# controller_tcan334gdcnt.net
KiCad netlist of a schematic drawn in EAGLE
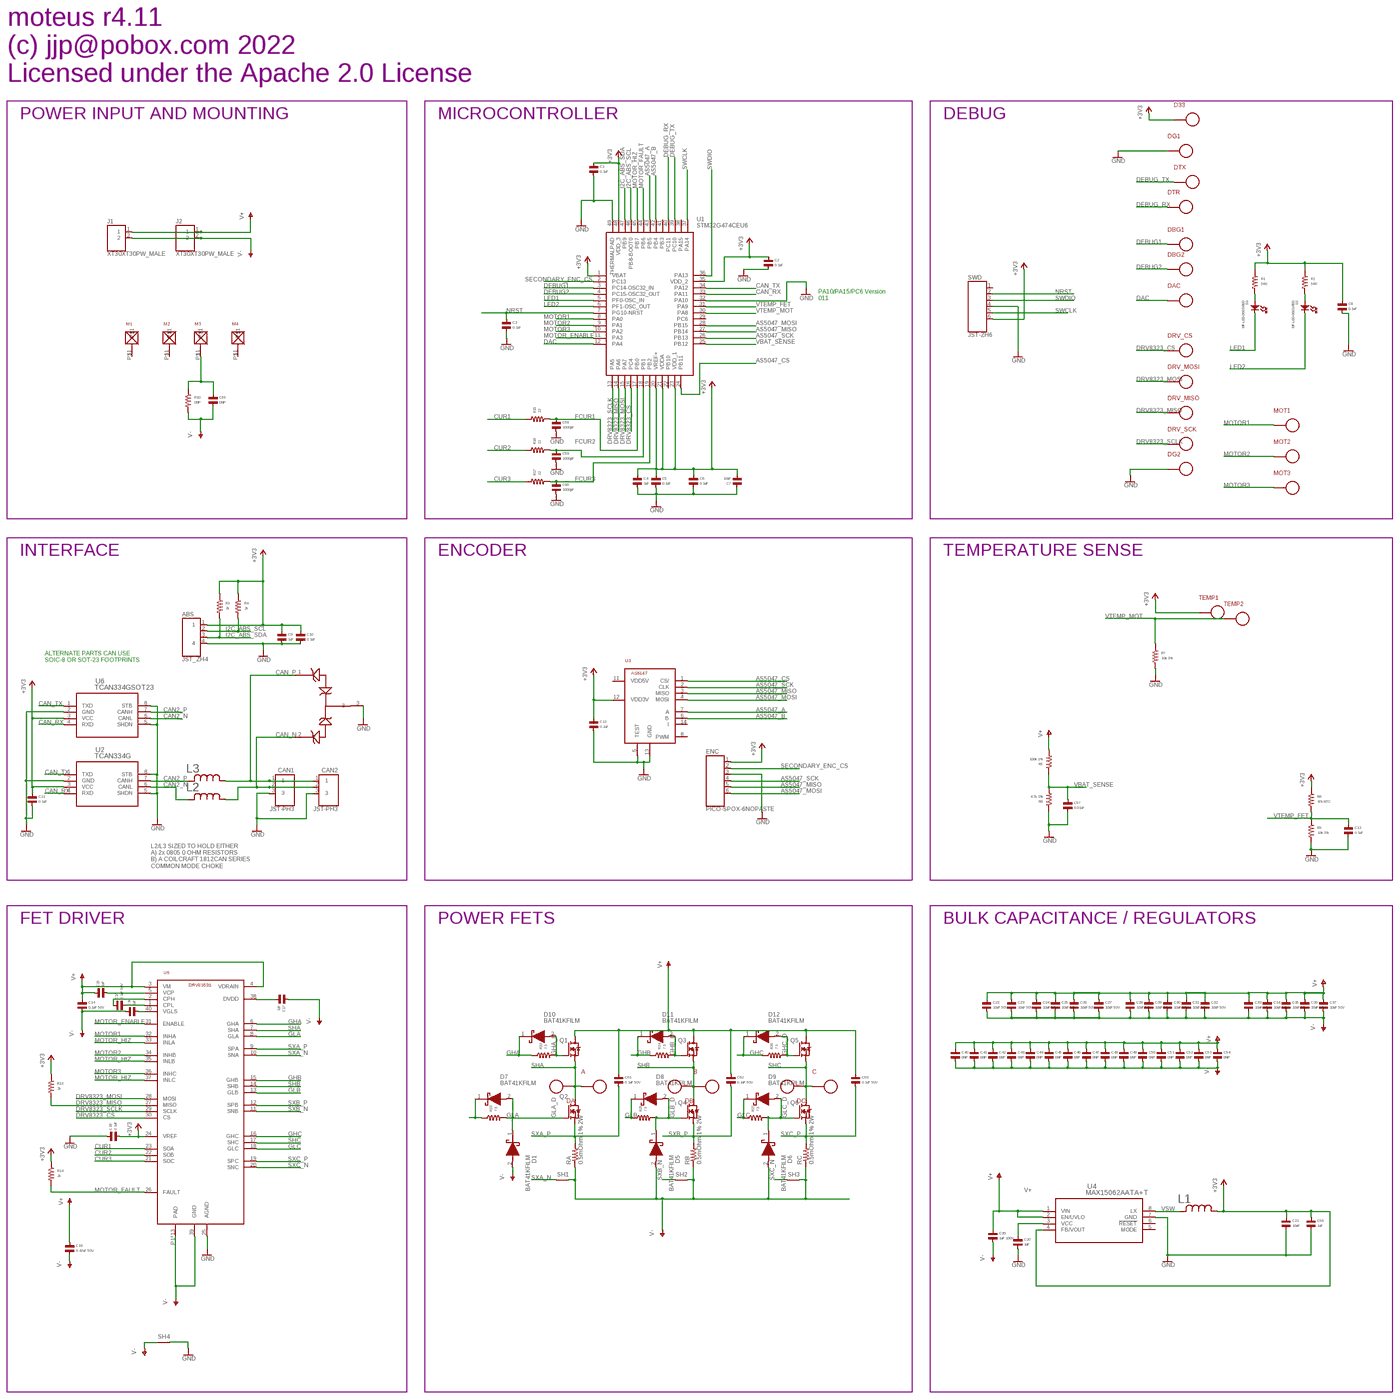
[diagram p0: schematic, sheet 1, overview]
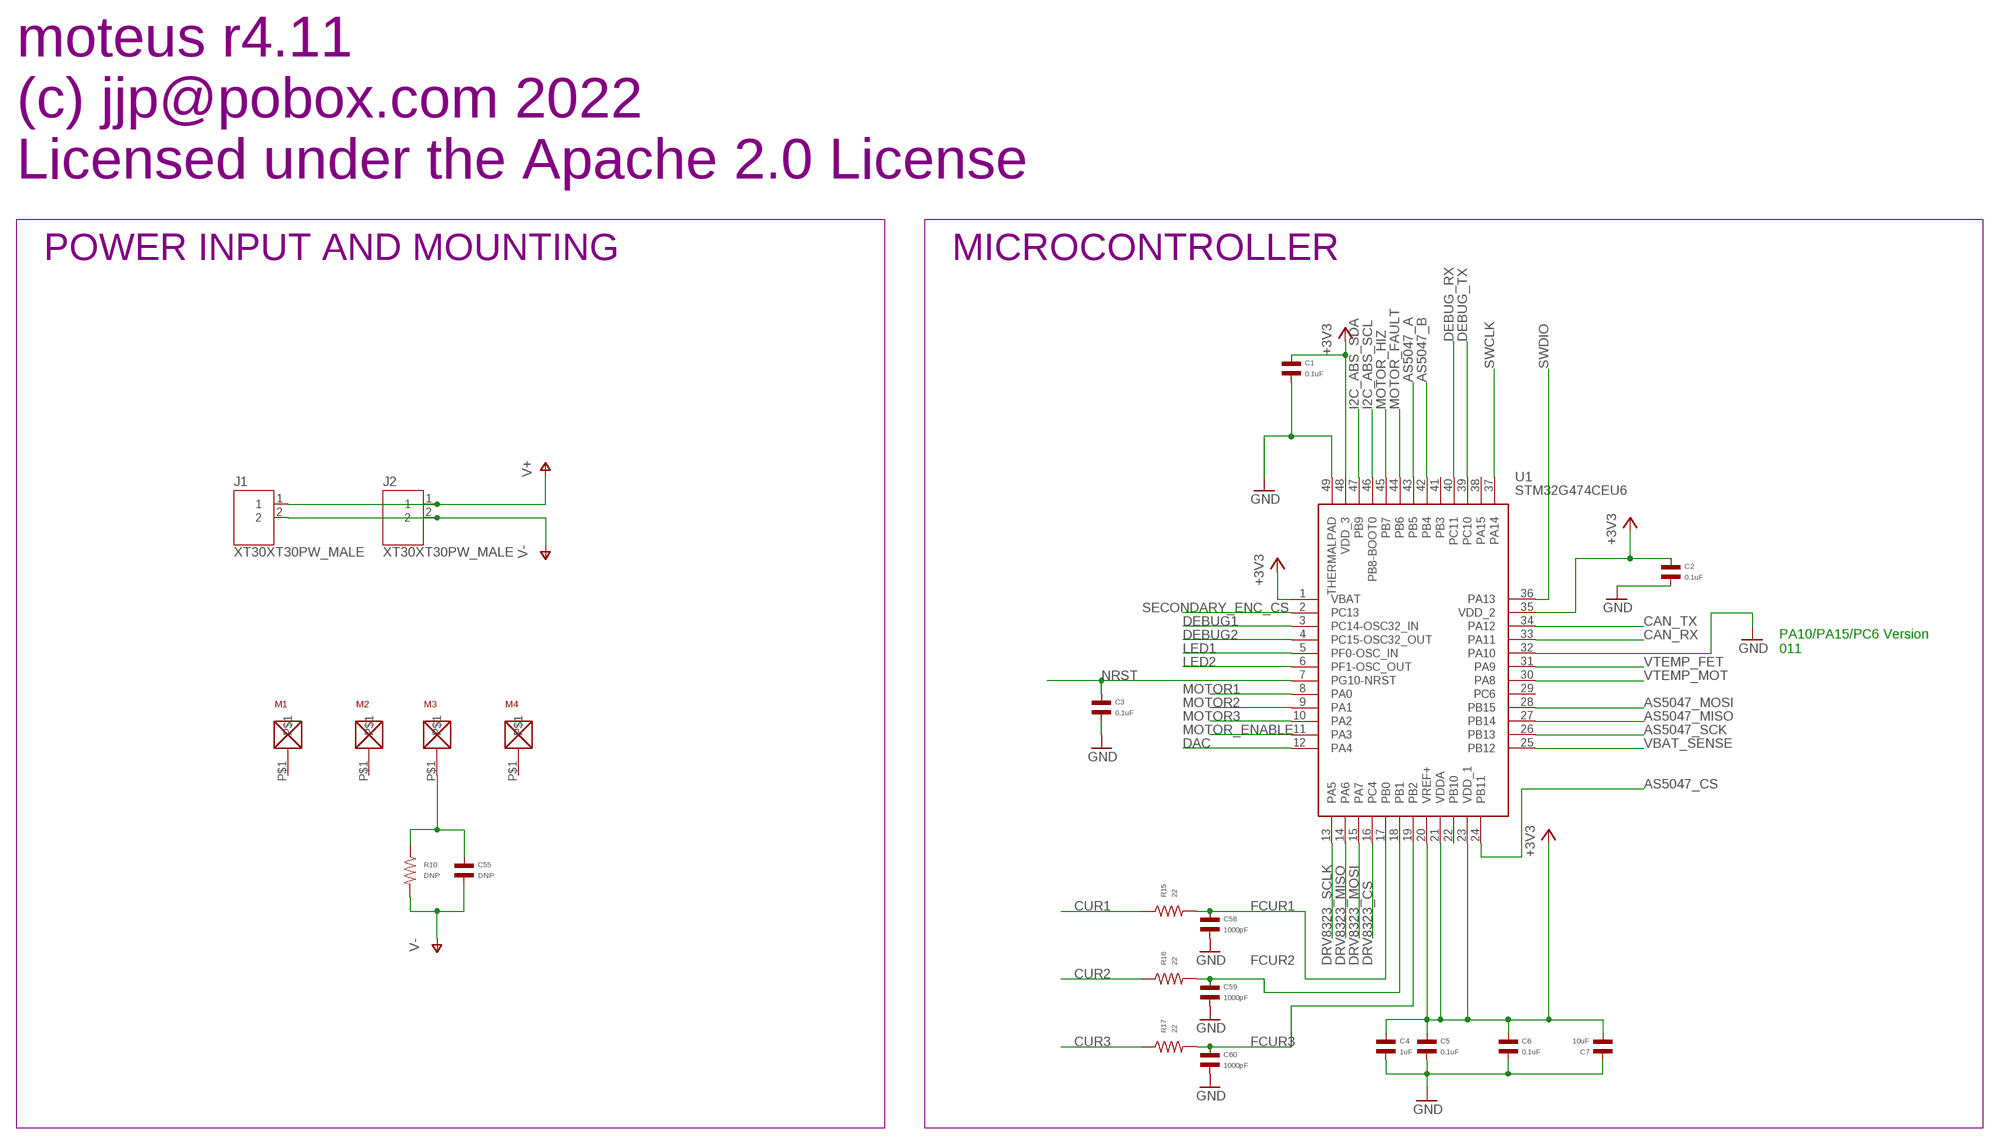
[diagram p1: schematic, sheet 1, part 1 of 4]
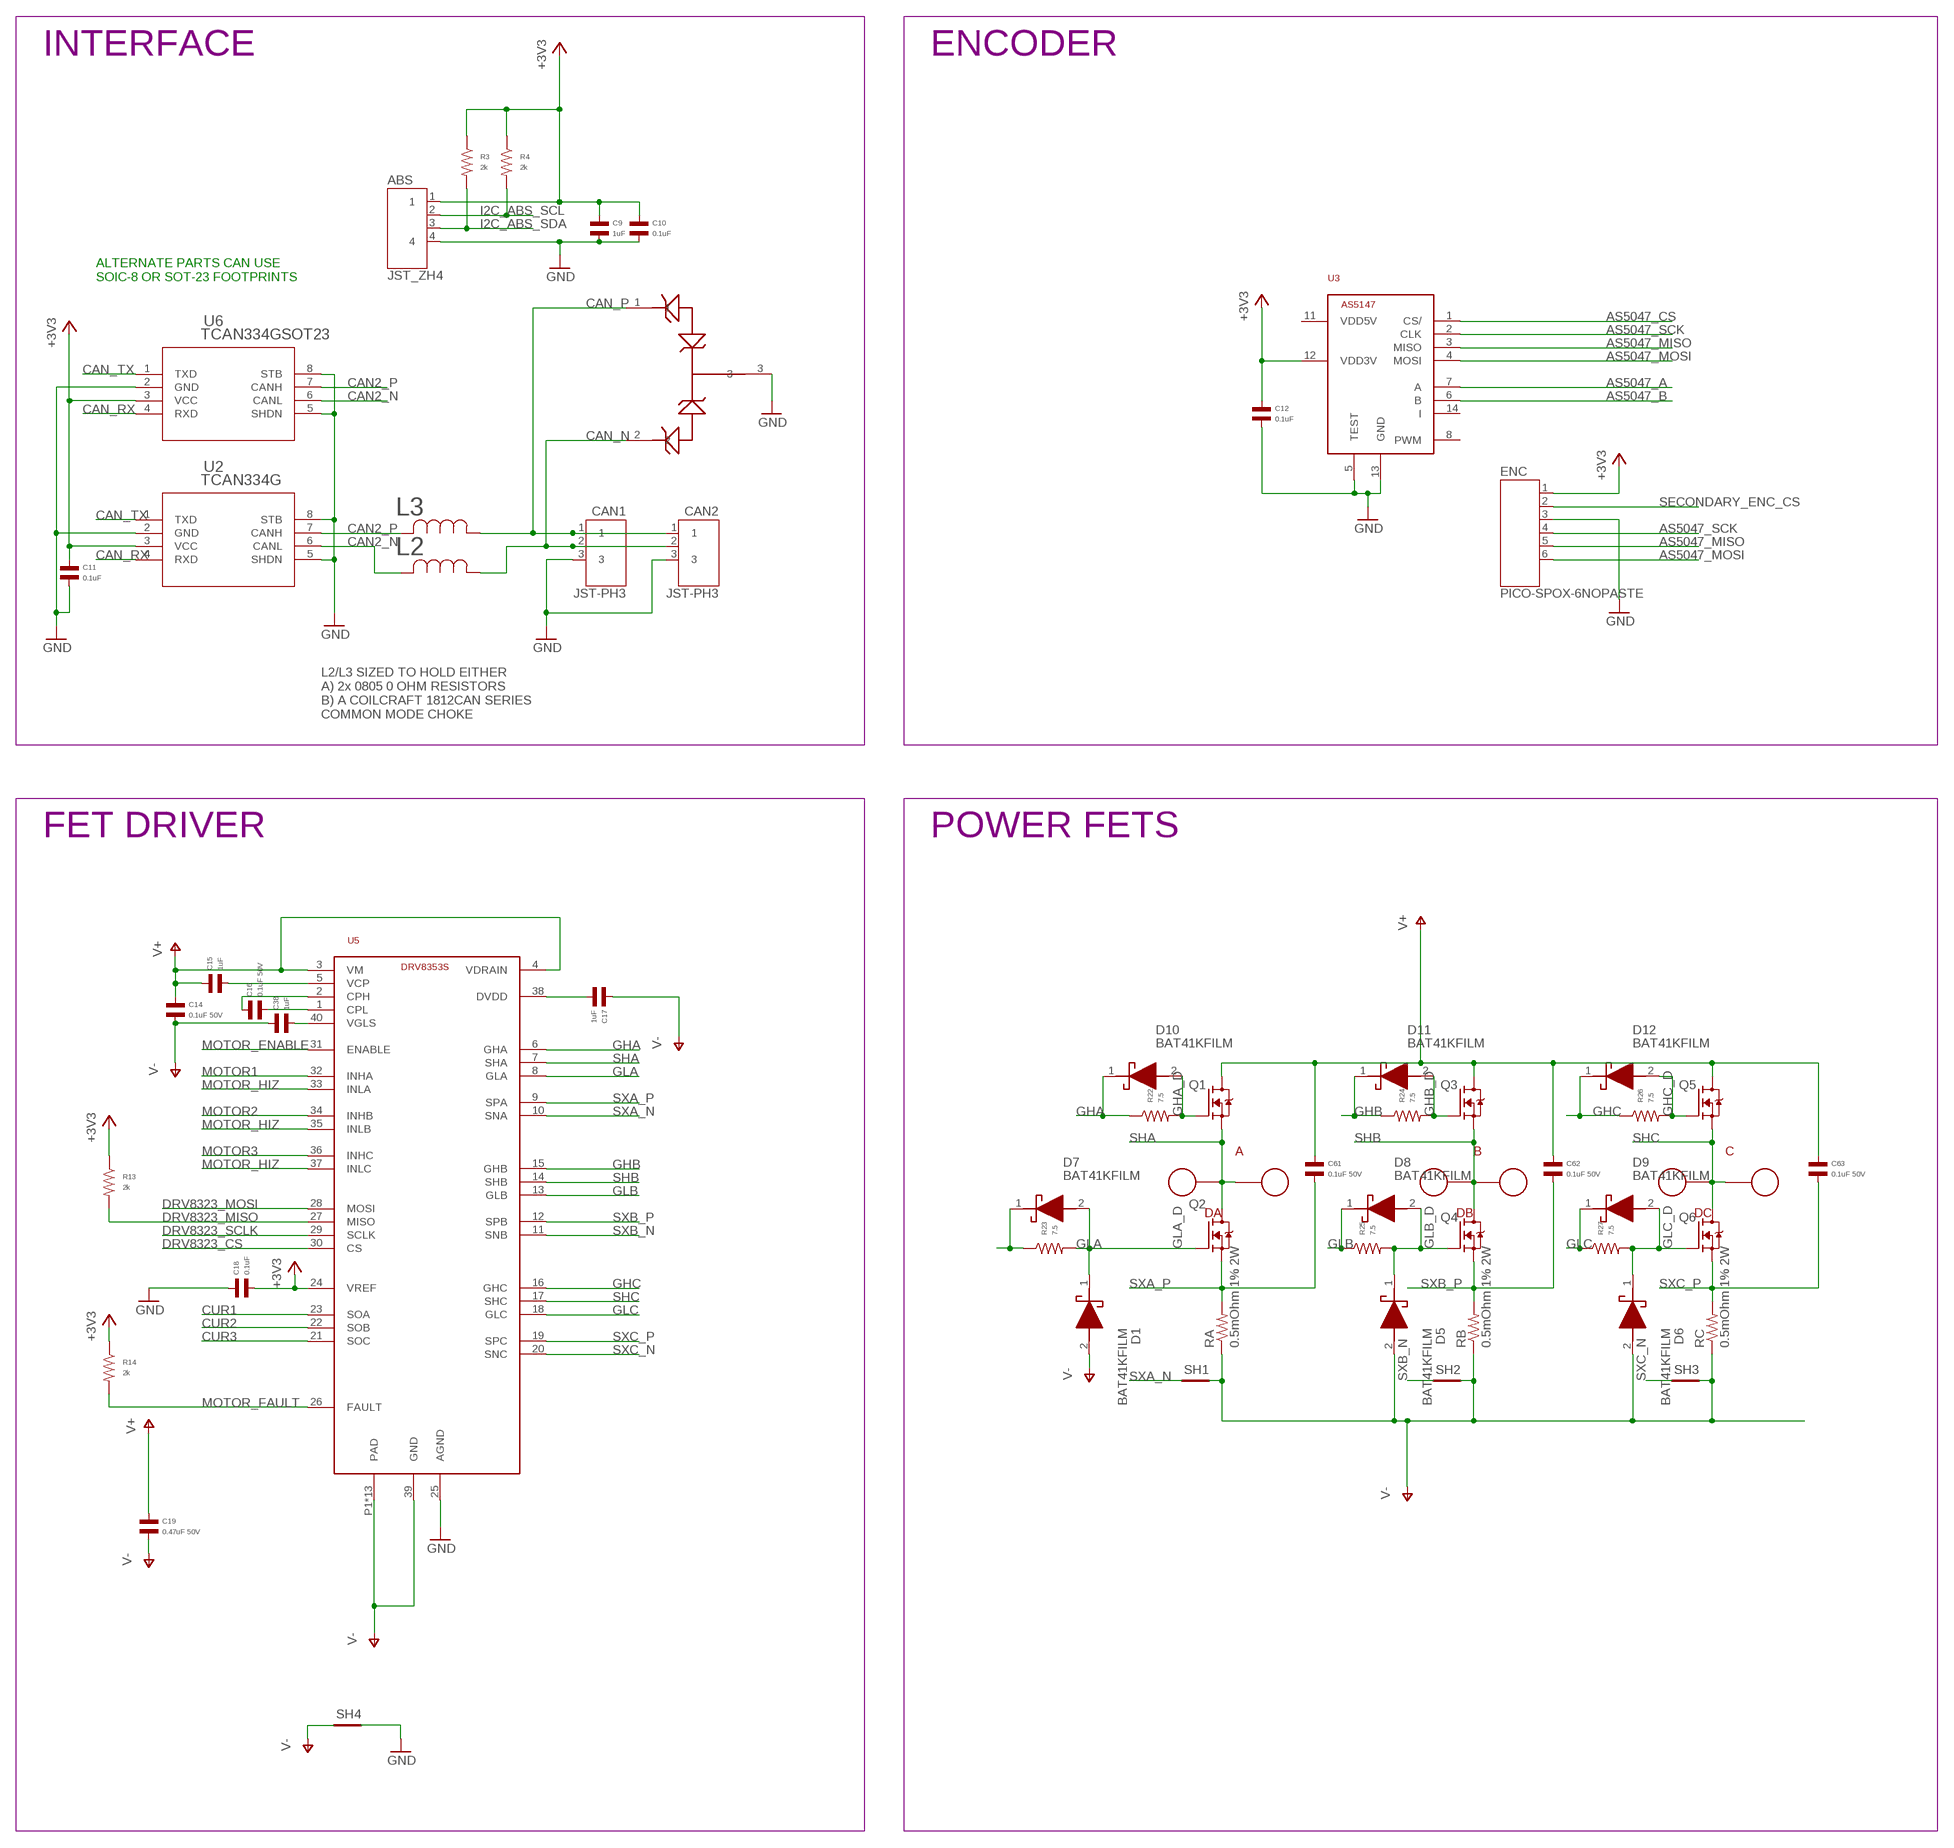
[diagram p2: schematic, sheet 1, part 2 of 4]
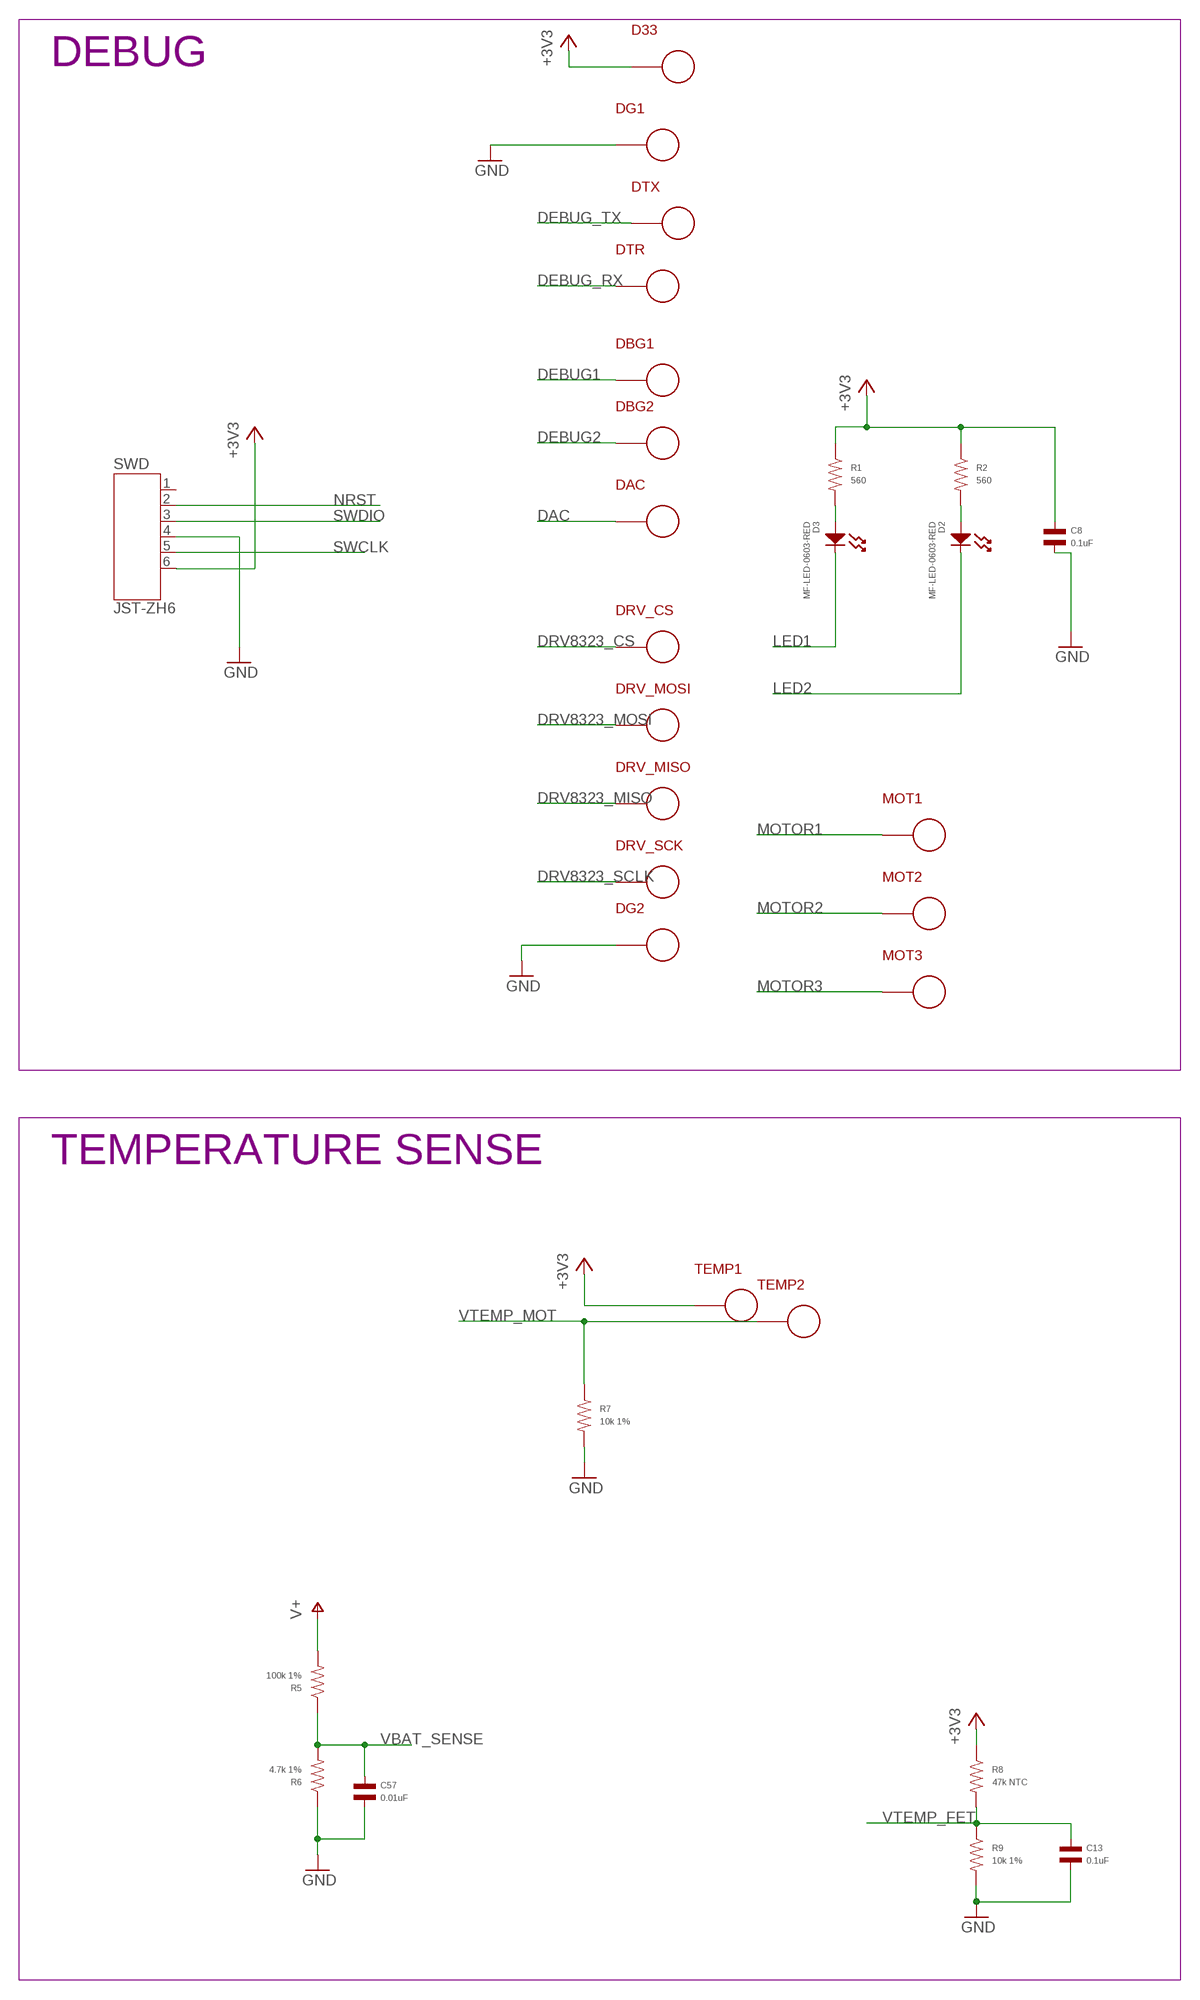
[diagram p3: schematic, sheet 1, part 3 of 4]
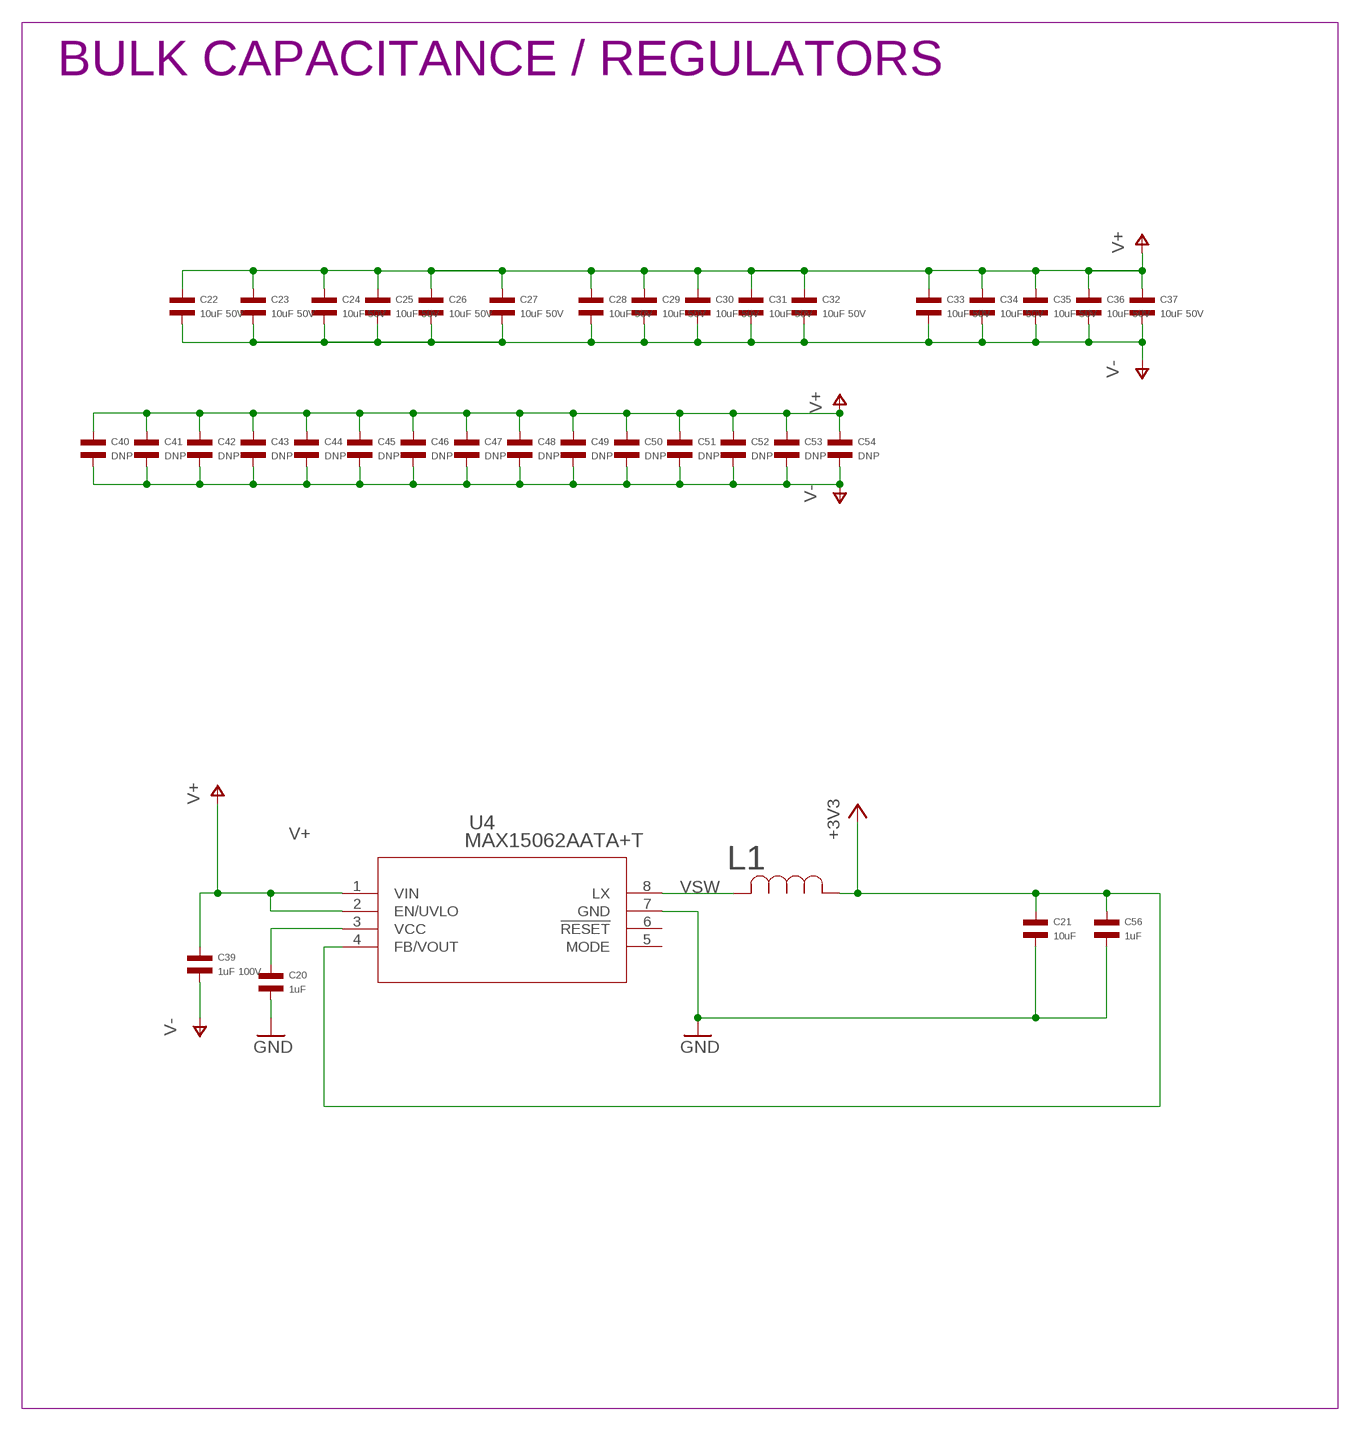
[diagram p4: schematic, sheet 1, part 4 of 4]

(export (version "E")
  (design (tool "Eeschema 10.0.6"))
  (components
    (comp (ref "A")
      (value "PAD16AWG_PAD")
      (footprint "eagle-import:16AWG_PAD")
      (libsource (lib "eagle-import") (part "PAD16AWG_PAD"))
    )
    (comp (ref "ABS")
      (value "JST_ZH4")
      (footprint "eagle-import:JST_S4B-ZR-SM4A-TF(LF)(SN)")
      (fields (field (name "MF") "JST") (field (name "MPN") "S4B-ZR-SM4A-TF(LF)(SN)"))
      (libsource (lib "eagle-import") (part "JST_ZH4"))
    )
    (comp (ref "B")
      (value "PAD16AWG_PAD")
      (footprint "eagle-import:16AWG_PAD")
      (libsource (lib "eagle-import") (part "PAD16AWG_PAD"))
    )
    (comp (ref "C")
      (value "PAD16AWG_PAD")
      (footprint "eagle-import:16AWG_PAD")
      (libsource (lib "eagle-import") (part "PAD16AWG_PAD"))
    )
    (comp (ref "C1")
      (value "0.1uF")
      (footprint "eagle-import:C0402")
      (fields (field (name "HOUSEPART") "YES") (field (name "MPN") "MF-CAP-0402-0.1uF"))
      (libsource (lib "eagle-import") (part "mfpassives_CAPACITOR_NP_0402"))
    )
    (comp (ref "C2")
      (value "0.1uF")
      (footprint "eagle-import:C0402")
      (fields (field (name "HOUSEPART") "YES") (field (name "MPN") "MF-CAP-0402-0.1uF"))
      (libsource (lib "eagle-import") (part "mfpassives_CAPACITOR_NP_0402"))
    )
    (comp (ref "C3")
      (value "0.1uF")
      (footprint "eagle-import:C0402")
      (fields (field (name "HOUSEPART") "YES") (field (name "MPN") "MF-CAP-0402-0.1uF"))
      (libsource (lib "eagle-import") (part "mfpassives_CAPACITOR_NP_0402"))
    )
    (comp (ref "C4")
      (value "1uF")
      (footprint "eagle-import:C0402")
      (fields (field (name "HOUSEPART") "YES") (field (name "MPN") "MF-CAP-0402-1uF"))
      (libsource (lib "eagle-import") (part "mfpassives_CAPACITOR_NP_0402"))
    )
    (comp (ref "C5")
      (value "0.1uF")
      (footprint "eagle-import:C0402")
      (fields (field (name "HOUSEPART") "YES") (field (name "MPN") "MF-CAP-0402-0.1uF"))
      (libsource (lib "eagle-import") (part "mfpassives_CAPACITOR_NP_0402"))
    )
    (comp (ref "C6")
      (value "0.1uF")
      (footprint "eagle-import:C0402")
      (fields (field (name "HOUSEPART") "YES") (field (name "MPN") "MF-CAP-0402-0.1uF"))
      (libsource (lib "eagle-import") (part "mfpassives_CAPACITOR_NP_0402"))
    )
    (comp (ref "C7")
      (value "10uF")
      (footprint "eagle-import:C1206")
      (fields (field (name "HOUSEPART") "YES") (field (name "MPN") "MF-CAP-1206-10uF"))
      (libsource (lib "eagle-import") (part "mfpassives_CAPACITOR_NP_1206"))
    )
    (comp (ref "C8")
      (value "0.1uF")
      (footprint "eagle-import:C0402")
      (fields (field (name "HOUSEPART") "YES") (field (name "MPN") "MF-CAP-0402-0.1uF"))
      (libsource (lib "eagle-import") (part "mfpassives_CAPACITOR_NP_0402"))
    )
    (comp (ref "C9")
      (value "1uF")
      (footprint "eagle-import:C0402")
      (fields (field (name "HOUSEPART") "YES") (field (name "MPN") "MF-CAP-0402-1uF"))
      (libsource (lib "eagle-import") (part "mfpassives_CAPACITOR_NP_0402"))
    )
    (comp (ref "C10")
      (value "0.1uF")
      (footprint "eagle-import:C0402")
      (fields (field (name "HOUSEPART") "YES") (field (name "MPN") "MF-CAP-0402-0.1uF"))
      (libsource (lib "eagle-import") (part "mfpassives_CAPACITOR_NP_0402"))
    )
    (comp (ref "C11")
      (value "0.1uF")
      (footprint "eagle-import:C0402_NOBORDER")
      (fields (field (name "HOUSEPART") "YES") (field (name "MPN") "MF-CAP-0402-0.1uF"))
      (libsource (lib "eagle-import") (part "CAPACITOR_NP_0402_NOBORDER"))
    )
    (comp (ref "C12")
      (value "0.1uF")
      (footprint "eagle-import:C0402")
      (fields (field (name "HOUSEPART") "YES") (field (name "MPN") "MF-CAP-0402-0.1uF"))
      (libsource (lib "eagle-import") (part "mfpassives_CAPACITOR_NP_0402"))
    )
    (comp (ref "C13")
      (value "0.1uF")
      (footprint "eagle-import:C0402")
      (fields (field (name "HOUSEPART") "YES") (field (name "MPN") "MF-CAP-0402-0.1uF"))
      (libsource (lib "eagle-import") (part "mfpassives_CAPACITOR_NP_0402"))
    )
    (comp (ref "C14")
      (value "0.1uF 50V")
      (footprint "eagle-import:C0402")
      (fields (field (name "MF") "TDK") (field (name "MPN") "CGA2B3X7R1H104K050BB"))
      (libsource (lib "eagle-import") (part "mfpassives_CAPACITOR_NP_0402"))
    )
    (comp (ref "C15")
      (value "1uF")
      (footprint "eagle-import:C0402")
      (fields (field (name "HOUSEPART") "YES") (field (name "MPN") "MF-CAP-0402-1uF"))
      (libsource (lib "eagle-import") (part "mfpassives_CAPACITOR_NP_0402"))
    )
    (comp (ref "C16")
      (value "0.1uF 50V")
      (footprint "eagle-import:C0402")
      (fields (field (name "MF") "TDK") (field (name "MPN") "CGA2B3X7R1H104K050BB"))
      (libsource (lib "eagle-import") (part "mfpassives_CAPACITOR_NP_0402"))
    )
    (comp (ref "C17")
      (value "1uF")
      (footprint "eagle-import:C0402")
      (fields (field (name "HOUSEPART") "YES") (field (name "MPN") "MF-CAP-0402-1uF"))
      (libsource (lib "eagle-import") (part "mfpassives_CAPACITOR_NP_0402"))
    )
    (comp (ref "C18")
      (value "0.1uF")
      (footprint "eagle-import:C0402")
      (fields (field (name "HOUSEPART") "YES") (field (name "MPN") "MF-CAP-0402-0.1uF"))
      (libsource (lib "eagle-import") (part "mfpassives_CAPACITOR_NP_0402"))
    )
    (comp (ref "C19")
      (value "0.47uF 50V")
      (footprint "eagle-import:C0402")
      (fields (field (name "MF") "Murata") (field (name "MPN") "GRM155R61H474KE11D"))
      (libsource (lib "eagle-import") (part "mfpassives_CAPACITOR_NP_0402"))
    )
    (comp (ref "C20")
      (value "1uF")
      (footprint "eagle-import:C0603")
      (fields (field (name "HOUSEPART") "1") (field (name "MPN") "MF-CAP-0603-1uF"))
      (libsource (lib "eagle-import") (part "mfpassives_CAPACITOR_NP_0603"))
    )
    (comp (ref "C21")
      (value "10uF")
      (footprint "eagle-import:C1206")
      (fields (field (name "HOUSEPART") "1") (field (name "MPN") "MF-CAP-1206-10uF"))
      (libsource (lib "eagle-import") (part "mfpassives_CAPACITOR_NP_1206"))
    )
    (comp (ref "C22")
      (value "10uF 50V")
      (footprint "eagle-import:C1206")
      (fields (field (name "MF") "TDK") (field (name "MPN") "C3216X7R1H106K160AE"))
      (libsource (lib "eagle-import") (part "mfpassives_CAPACITOR_NP_1206"))
    )
    (comp (ref "C23")
      (value "10uF 50V")
      (footprint "eagle-import:C1206")
      (fields (field (name "MF") "TDK") (field (name "MPN") "C3216X7R1H106K160AE"))
      (libsource (lib "eagle-import") (part "mfpassives_CAPACITOR_NP_1206"))
    )
    (comp (ref "C24")
      (value "10uF 50V")
      (footprint "eagle-import:C1206")
      (fields (field (name "MF") "TDK") (field (name "MPN") "C3216X7R1H106K160AE"))
      (libsource (lib "eagle-import") (part "mfpassives_CAPACITOR_NP_1206"))
    )
    (comp (ref "C25")
      (value "10uF 50V")
      (footprint "eagle-import:C1206")
      (fields (field (name "MF") "TDK") (field (name "MPN") "C3216X7R1H106K160AE"))
      (libsource (lib "eagle-import") (part "mfpassives_CAPACITOR_NP_1206"))
    )
    (comp (ref "C26")
      (value "10uF 50V")
      (footprint "eagle-import:C1206")
      (fields (field (name "MF") "TDK") (field (name "MPN") "C3216X7R1H106K160AE"))
      (libsource (lib "eagle-import") (part "mfpassives_CAPACITOR_NP_1206"))
    )
    (comp (ref "C27")
      (value "10uF 50V")
      (footprint "eagle-import:C1206")
      (fields (field (name "MF") "TDK") (field (name "MPN") "C3216X7R1H106K160AE"))
      (libsource (lib "eagle-import") (part "mfpassives_CAPACITOR_NP_1206"))
    )
    (comp (ref "C28")
      (value "10uF 50V")
      (footprint "eagle-import:C1206")
      (fields (field (name "MF") "TDK") (field (name "MPN") "C3216X7R1H106K160AE"))
      (libsource (lib "eagle-import") (part "mfpassives_CAPACITOR_NP_1206"))
    )
    (comp (ref "C29")
      (value "10uF 50V")
      (footprint "eagle-import:C1206")
      (fields (field (name "MF") "TDK") (field (name "MPN") "C3216X7R1H106K160AE"))
      (libsource (lib "eagle-import") (part "mfpassives_CAPACITOR_NP_1206"))
    )
    (comp (ref "C30")
      (value "10uF 50V")
      (footprint "eagle-import:C1206")
      (fields (field (name "MF") "TDK") (field (name "MPN") "C3216X7R1H106K160AE"))
      (libsource (lib "eagle-import") (part "mfpassives_CAPACITOR_NP_1206"))
    )
    (comp (ref "C31")
      (value "10uF 50V")
      (footprint "eagle-import:C1206")
      (fields (field (name "MF") "TDK") (field (name "MPN") "C3216X7R1H106K160AE"))
      (libsource (lib "eagle-import") (part "mfpassives_CAPACITOR_NP_1206"))
    )
    (comp (ref "C32")
      (value "10uF 50V")
      (footprint "eagle-import:C1206")
      (fields (field (name "MF") "TDK") (field (name "MPN") "C3216X7R1H106K160AE"))
      (libsource (lib "eagle-import") (part "mfpassives_CAPACITOR_NP_1206"))
    )
    (comp (ref "C33")
      (value "10uF 50V")
      (footprint "eagle-import:C1206")
      (fields (field (name "MF") "TDK") (field (name "MPN") "C3216X7R1H106K160AE"))
      (libsource (lib "eagle-import") (part "mfpassives_CAPACITOR_NP_1206"))
    )
    (comp (ref "C34")
      (value "10uF 50V")
      (footprint "eagle-import:C1206")
      (fields (field (name "MF") "TDK") (field (name "MPN") "C3216X7R1H106K160AE"))
      (libsource (lib "eagle-import") (part "mfpassives_CAPACITOR_NP_1206"))
    )
    (comp (ref "C35")
      (value "10uF 50V")
      (footprint "eagle-import:C1206_NOBORDER")
      (fields (field (name "MF") "TDK") (field (name "MPN") "C3216X7R1H106K160AE"))
      (libsource (lib "eagle-import") (part "CAPACITOR_NP_1206_NOBORDER"))
    )
    (comp (ref "C36")
      (value "10uF 50V")
      (footprint "eagle-import:C1206")
      (fields (field (name "MF") "TDK") (field (name "MPN") "C3216X7R1H106K160AE"))
      (libsource (lib "eagle-import") (part "mfpassives_CAPACITOR_NP_1206"))
    )
    (comp (ref "C37")
      (value "10uF 50V")
      (footprint "eagle-import:C1206")
      (fields (field (name "MF") "TDK") (field (name "MPN") "C3216X7R1H106K160AE"))
      (libsource (lib "eagle-import") (part "mfpassives_CAPACITOR_NP_1206"))
    )
    (comp (ref "C38")
      (value "1uF")
      (footprint "eagle-import:C0603")
      (fields
        (field (name "HOUSEPART") "YES")
        (field (name "MF") "TDK")
        (field (name "MPN") "C1608X7R1E105K080AE")
      )
      (libsource (lib "eagle-import") (part "mfpassives_CAPACITOR_NP_0603"))
    )
    (comp (ref "C39")
      (value "1uF 100V")
      (footprint "eagle-import:C0805")
      (fields (field (name "MF") "MURATA") (field (name "MPN") "GCM21BC72A105KE36L"))
      (libsource (lib "eagle-import") (part "mfpassives_CAPACITOR_NP_0805"))
    )
    (comp (ref "C40")
      (value "DNP")
      (footprint "eagle-import:C1206_NOCREAM")
      (libsource (lib "eagle-import") (part "CAPACITOR_NP_1206_NOCREAM"))
    )
    (comp (ref "C41")
      (value "DNP")
      (footprint "eagle-import:C1206_NOCREAM")
      (libsource (lib "eagle-import") (part "CAPACITOR_NP_1206_NOCREAM"))
    )
    (comp (ref "C42")
      (value "DNP")
      (footprint "eagle-import:C1206_NOCREAM")
      (libsource (lib "eagle-import") (part "CAPACITOR_NP_1206_NOCREAM"))
    )
    (comp (ref "C43")
      (value "DNP")
      (footprint "eagle-import:C1206_NOCREAM")
      (libsource (lib "eagle-import") (part "CAPACITOR_NP_1206_NOCREAM"))
    )
    (comp (ref "C44")
      (value "DNP")
      (footprint "eagle-import:C1206_NOCREAM")
      (libsource (lib "eagle-import") (part "CAPACITOR_NP_1206_NOCREAM"))
    )
    (comp (ref "C45")
      (value "DNP")
      (footprint "eagle-import:C1206_NOCREAM")
      (libsource (lib "eagle-import") (part "CAPACITOR_NP_1206_NOCREAM"))
    )
    (comp (ref "C46")
      (value "DNP")
      (footprint "eagle-import:C1206_NOCREAM")
      (libsource (lib "eagle-import") (part "CAPACITOR_NP_1206_NOCREAM"))
    )
    (comp (ref "C47")
      (value "DNP")
      (footprint "eagle-import:C1206_NOCREAM")
      (libsource (lib "eagle-import") (part "CAPACITOR_NP_1206_NOCREAM"))
    )
    (comp (ref "C48")
      (value "DNP")
      (footprint "eagle-import:C1206_NOCREAM")
      (libsource (lib "eagle-import") (part "CAPACITOR_NP_1206_NOCREAM"))
    )
    (comp (ref "C49")
      (value "DNP")
      (footprint "eagle-import:C1206_NOCREAM")
      (libsource (lib "eagle-import") (part "CAPACITOR_NP_1206_NOCREAM"))
    )
    (comp (ref "C50")
      (value "DNP")
      (footprint "eagle-import:C1206_NOCREAM")
      (libsource (lib "eagle-import") (part "CAPACITOR_NP_1206_NOCREAM"))
    )
    (comp (ref "C51")
      (value "DNP")
      (footprint "eagle-import:C1206_NOCREAM")
      (libsource (lib "eagle-import") (part "CAPACITOR_NP_1206_NOCREAM"))
    )
    (comp (ref "C52")
      (value "DNP")
      (footprint "eagle-import:C1206_NOCREAM")
      (libsource (lib "eagle-import") (part "CAPACITOR_NP_1206_NOCREAM"))
    )
    (comp (ref "C53")
      (value "DNP")
      (footprint "eagle-import:C1206_NOCREAM")
      (libsource (lib "eagle-import") (part "CAPACITOR_NP_1206_NOCREAM"))
    )
    (comp (ref "C54")
      (value "DNP")
      (footprint "eagle-import:C1206_NOCREAM")
      (libsource (lib "eagle-import") (part "CAPACITOR_NP_1206_NOCREAM"))
    )
    (comp (ref "C55")
      (value "DNP")
      (footprint "eagle-import:C0402")
      (fields (field (name "POPULATE") "0"))
      (libsource (lib "eagle-import") (part "mfpassives_CAPACITOR_NP_0402"))
    )
    (comp (ref "C56")
      (value "1uF")
      (footprint "eagle-import:C0402")
      (fields (field (name "HOUSEPART") "YES") (field (name "MPN") "MF-CAP-0402-1uF"))
      (libsource (lib "eagle-import") (part "mfpassives_CAPACITOR_NP_0402"))
    )
    (comp (ref "C57")
      (value "0.01uF")
      (footprint "eagle-import:C0402")
      (fields (field (name "HOUSEPART") "YES") (field (name "MPN") "MF-CAP-0402-0.01uF"))
      (libsource (lib "eagle-import") (part "mfpassives_CAPACITOR_NP_0402"))
    )
    (comp (ref "C58")
      (value "1000pF")
      (footprint "eagle-import:C0402_NOBORDER")
      (fields (field (name "HOUSEPART") "1") (field (name "MPN") "MF-CAP-0402-1nF"))
      (libsource (lib "eagle-import") (part "CAPACITOR_NP_0402_NOBORDER"))
    )
    (comp (ref "C59")
      (value "1000pF")
      (footprint "eagle-import:C0402_NOBORDER")
      (fields (field (name "HOUSEPART") "1") (field (name "MPN") "MF-CAP-0402-1nF"))
      (libsource (lib "eagle-import") (part "CAPACITOR_NP_0402_NOBORDER"))
    )
    (comp (ref "C60")
      (value "1000pF")
      (footprint "eagle-import:C0402_NOBORDER")
      (fields (field (name "HOUSEPART") "1") (field (name "MPN") "MF-CAP-0402-1nF"))
      (libsource (lib "eagle-import") (part "CAPACITOR_NP_0402_NOBORDER"))
    )
    (comp (ref "C61")
      (value "0.1uF 50V")
      (footprint "eagle-import:C1206")
      (fields (field (name "MF") "KYOCERA AVX") (field (name "MPN") "12065C104KAZ2A"))
      (libsource (lib "eagle-import") (part "mfpassives_CAPACITOR_NP_1206"))
    )
    (comp (ref "C62")
      (value "0.1uF 50V")
      (footprint "eagle-import:C0603_NOBORDER")
      (fields (field (name "MF") "KYOCERA AVX") (field (name "MPN") "06035C104KAZ2A"))
      (libsource (lib "eagle-import") (part "CAPACITOR_NP_0603_NOBORDER"))
    )
    (comp (ref "C63")
      (value "0.1uF 50V")
      (footprint "eagle-import:C1206")
      (fields (field (name "MF") "KYOCERA AVX") (field (name "MPN") "12065C104KAZ2A"))
      (libsource (lib "eagle-import") (part "mfpassives_CAPACITOR_NP_1206"))
    )
    (comp (ref "CAN1")
      (value "JST-PH3")
      (footprint "eagle-import:JST_S3B-PH-SM4-TB(LF)(SN)")
      (fields (field (name "MF") "JST") (field (name "MPN") "S3B-PH-SM4-TB(LF)(SN)"))
      (libsource (lib "eagle-import") (part "JST-PH3"))
    )
    (comp (ref "CAN2")
      (value "JST-PH3")
      (footprint "eagle-import:JST_S3B-PH-SM4-TB(LF)(SN)")
      (fields (field (name "MF") "JST") (field (name "MPN") "S3B-PH-SM4-TB(LF)(SN)"))
      (libsource (lib "eagle-import") (part "JST-PH3"))
    )
    (comp (ref "D1")
      (value "BAT41KFILM")
      (footprint "eagle-import:SODFL1608X70N")
      (fields (field (name "MOUSER_PART_NUMBER") "511-BAT41KFILM") (field (name "MF") "ST"))
      (libsource (lib "eagle-import") (part "BAT41KFILM"))
    )
    (comp (ref "D2")
      (value "MF-LED-0603-RED")
      (footprint "eagle-import:LED0603")
      (fields (field (name "HOUSEPART") "YES") (field (name "MPN") "MF-LED-0603-GREEN"))
      (libsource (lib "eagle-import") (part "LED_SINGLE-0603-RED"))
    )
    (comp (ref "D3")
      (value "MF-LED-0603-RED")
      (footprint "eagle-import:LED0603")
      (fields (field (name "HOUSEPART") "YES"))
      (libsource (lib "eagle-import") (part "LED_SINGLE-0603-RED"))
    )
    (comp (ref "D4")
      (value "DUAL_TVS")
      (footprint "eagle-import:SOT23-3")
      (fields (field (name "MPN") "CDSOT23-0502B"))
      (libsource (lib "eagle-import") (part "DUAL_TVS"))
    )
    (comp (ref "D5")
      (value "BAT41KFILM")
      (footprint "eagle-import:SODFL1608X70N")
      (fields (field (name "MOUSER_PART_NUMBER") "511-BAT41KFILM") (field (name "MF") "ST"))
      (libsource (lib "eagle-import") (part "BAT41KFILM"))
    )
    (comp (ref "D6")
      (value "BAT41KFILM")
      (footprint "eagle-import:SODFL1608X70N")
      (fields (field (name "MOUSER_PART_NUMBER") "511-BAT41KFILM") (field (name "MF") "ST"))
      (libsource (lib "eagle-import") (part "BAT41KFILM"))
    )
    (comp (ref "D7")
      (value "BAT41KFILM")
      (footprint "eagle-import:SODFL1608X70N")
      (fields (field (name "MOUSER_PART_NUMBER") "511-BAT41KFILM") (field (name "MF") "ST"))
      (libsource (lib "eagle-import") (part "BAT41KFILM"))
    )
    (comp (ref "D8")
      (value "BAT41KFILM")
      (footprint "eagle-import:SODFL1608X70N")
      (fields (field (name "MOUSER_PART_NUMBER") "511-BAT41KFILM") (field (name "MF") "ST"))
      (libsource (lib "eagle-import") (part "BAT41KFILM"))
    )
    (comp (ref "D9")
      (value "BAT41KFILM")
      (footprint "eagle-import:SODFL1608X70N")
      (fields (field (name "MOUSER_PART_NUMBER") "511-BAT41KFILM") (field (name "MF") "ST"))
      (libsource (lib "eagle-import") (part "BAT41KFILM"))
    )
    (comp (ref "D10")
      (value "BAT41KFILM")
      (footprint "eagle-import:SODFL1608X70N")
      (fields (field (name "MOUSER_PART_NUMBER") "511-BAT41KFILM") (field (name "MF") "ST"))
      (libsource (lib "eagle-import") (part "BAT41KFILM"))
    )
    (comp (ref "D11")
      (value "BAT41KFILM")
      (footprint "eagle-import:SODFL1608X70N")
      (fields (field (name "MOUSER_PART_NUMBER") "511-BAT41KFILM") (field (name "MF") "ST"))
      (libsource (lib "eagle-import") (part "BAT41KFILM"))
    )
    (comp (ref "D12")
      (value "BAT41KFILM")
      (footprint "eagle-import:SODFL1608X70N")
      (fields (field (name "MOUSER_PART_NUMBER") "511-BAT41KFILM") (field (name "MF") "ST"))
      (libsource (lib "eagle-import") (part "BAT41KFILM"))
    )
    (comp (ref "D33")
      (value "PAD24AWG_PAD")
      (footprint "eagle-import:24AWG_PAD")
      (libsource (lib "eagle-import") (part "PAD24AWG_PAD"))
    )
    (comp (ref "DA")
      (value "PAD24AWG_PAD")
      (footprint "eagle-import:24AWG_PAD")
      (libsource (lib "eagle-import") (part "PAD24AWG_PAD"))
    )
    (comp (ref "DAC")
      (value "PAD24AWG_PAD")
      (footprint "eagle-import:24AWG_PAD")
      (libsource (lib "eagle-import") (part "PAD24AWG_PAD"))
    )
    (comp (ref "DB")
      (value "PAD24AWG_PAD")
      (footprint "eagle-import:24AWG_PAD")
      (libsource (lib "eagle-import") (part "PAD24AWG_PAD"))
    )
    (comp (ref "DBG1")
      (value "PAD24AWG_PAD")
      (footprint "eagle-import:24AWG_PAD")
      (libsource (lib "eagle-import") (part "PAD24AWG_PAD"))
    )
    (comp (ref "DBG2")
      (value "PAD24AWG_PAD")
      (footprint "eagle-import:24AWG_PAD")
      (libsource (lib "eagle-import") (part "PAD24AWG_PAD"))
    )
    (comp (ref "DC")
      (value "PAD24AWG_PAD")
      (footprint "eagle-import:24AWG_PAD")
      (libsource (lib "eagle-import") (part "PAD24AWG_PAD"))
    )
    (comp (ref "DG1")
      (value "PAD24AWG_PAD")
      (footprint "eagle-import:24AWG_PAD")
      (libsource (lib "eagle-import") (part "PAD24AWG_PAD"))
    )
    (comp (ref "DG2")
      (value "PAD24AWG_PAD")
      (footprint "eagle-import:24AWG_PAD")
      (libsource (lib "eagle-import") (part "PAD24AWG_PAD"))
    )
    (comp (ref "DRV_CS")
      (value "PAD24AWG_PAD")
      (footprint "eagle-import:24AWG_PAD")
      (libsource (lib "eagle-import") (part "PAD24AWG_PAD"))
    )
    (comp (ref "DRV_MISO")
      (value "PAD24AWG_PAD")
      (footprint "eagle-import:24AWG_PAD")
      (libsource (lib "eagle-import") (part "PAD24AWG_PAD"))
    )
    (comp (ref "DRV_MOSI")
      (value "PAD24AWG_PAD")
      (footprint "eagle-import:24AWG_PAD")
      (libsource (lib "eagle-import") (part "PAD24AWG_PAD"))
    )
    (comp (ref "DRV_SCK")
      (value "PAD24AWG_PAD")
      (footprint "eagle-import:24AWG_PAD")
      (libsource (lib "eagle-import") (part "PAD24AWG_PAD"))
    )
    (comp (ref "DTR")
      (value "PAD24AWG_PAD")
      (footprint "eagle-import:24AWG_PAD")
      (libsource (lib "eagle-import") (part "PAD24AWG_PAD"))
    )
    (comp (ref "DTX")
      (value "PAD24AWG_PAD")
      (footprint "eagle-import:24AWG_PAD")
      (libsource (lib "eagle-import") (part "PAD24AWG_PAD"))
    )
    (comp (ref "ENC")
      (value "PICO-SPOX-6NOPASTE")
      (footprint "eagle-import:PICO-SPOX-SMT-RA-6-NOPASTE")
      (libsource (lib "eagle-import") (part "PICO-SPOX-6NOPASTE"))
    )
    (comp (ref "J1")
      (value "XT30XT30PW_MALE")
      (footprint "eagle-import:XT30PW_MALE")
      (libsource (lib "eagle-import") (part "XT30XT30PW_MALE"))
    )
    (comp (ref "J2")
      (value "XT30XT30PW_MALE")
      (footprint "eagle-import:XT30PW_MALE")
      (libsource (lib "eagle-import") (part "XT30XT30PW_MALE"))
    )
    (comp (ref "L1")
      (value "SRN4018-220M")
      (footprint "eagle-import:IND_BOURNS_SRN4018")
      (fields
        (field (name "MANUFACTURER_PART_NUMBER") "SRN4018220M")
        (field (name "MANUFACTURER_PART_NUMBER_1") "SRN4018-330M")
        (field (name "MPN") "SRN4018-330M")
      )
      (libsource (lib "eagle-import") (part "SRN4018-220M"))
    )
    (comp (ref "L2")
      (value "HALF_CHOKE")
      (footprint "eagle-import:1812_COMMON_HALF")
      (fields (field (name "MPN") "MF-RES-0805-0"))
      (libsource (lib "eagle-import") (part "HALF_CHOKE"))
    )
    (comp (ref "L3")
      (value "HALF_CHOKE")
      (footprint "eagle-import:1812_COMMON_HALF")
      (fields (field (name "MPN") "MF-RES-0805-0"))
      (libsource (lib "eagle-import") (part "HALF_CHOKE"))
    )
    (comp (ref "M1")
      (value "MOUNT")
      (footprint "eagle-import:M2.5MOUNT")
      (libsource (lib "eagle-import") (part "MOUNT"))
    )
    (comp (ref "M2")
      (value "MOUNT")
      (footprint "eagle-import:M2.5MOUNT")
      (libsource (lib "eagle-import") (part "MOUNT"))
    )
    (comp (ref "M3")
      (value "MOUNT")
      (footprint "eagle-import:M2.5MOUNT")
      (libsource (lib "eagle-import") (part "MOUNT"))
    )
    (comp (ref "M4")
      (value "MOUNT")
      (footprint "eagle-import:M2.5MOUNT")
      (libsource (lib "eagle-import") (part "MOUNT"))
    )
    (comp (ref "MOT1")
      (value "PAD24AWG_PAD")
      (footprint "eagle-import:24AWG_PAD")
      (libsource (lib "eagle-import") (part "PAD24AWG_PAD"))
    )
    (comp (ref "MOT2")
      (value "PAD24AWG_PAD")
      (footprint "eagle-import:24AWG_PAD")
      (libsource (lib "eagle-import") (part "PAD24AWG_PAD"))
    )
    (comp (ref "MOT3")
      (value "PAD24AWG_PAD")
      (footprint "eagle-import:24AWG_PAD")
      (libsource (lib "eagle-import") (part "PAD24AWG_PAD"))
    )
    (comp (ref "Q1")
      (value "TPH1R204PLSOP_ADVANCE_8")
      (footprint "eagle-import:SOP_ADVANCE_8")
      (fields
        (field (name "MF") "Toshiba")
        (field (name "MPN") "TPH1R204PL")
        (field (name "MF_1") "Toshiba")
        (field (name "MPN_1") "TPH2R506PL,L1Q")
      )
      (libsource (lib "eagle-import") (part "TPH1R204PLSOP_ADVANCE_8"))
    )
    (comp (ref "Q2")
      (value "TPH1R204PLSOP_ADVANCE_8")
      (footprint "eagle-import:SOP_ADVANCE_8")
      (fields
        (field (name "MF") "Toshiba")
        (field (name "MPN") "TPH1R204PL")
        (field (name "MF_1") "Toshiba")
        (field (name "MPN_1") "TPH2R506PL,L1Q")
      )
      (libsource (lib "eagle-import") (part "TPH1R204PLSOP_ADVANCE_8"))
    )
    (comp (ref "Q3")
      (value "TPH1R204PLSOP_ADVANCE_8")
      (footprint "eagle-import:SOP_ADVANCE_8")
      (fields
        (field (name "MF") "Toshiba")
        (field (name "MPN") "TPH1R204PL")
        (field (name "MF_1") "Toshiba")
        (field (name "MPN_1") "TPH2R506PL,L1Q")
      )
      (libsource (lib "eagle-import") (part "TPH1R204PLSOP_ADVANCE_8"))
    )
    (comp (ref "Q4")
      (value "TPH1R204PLSOP_ADVANCE_8")
      (footprint "eagle-import:SOP_ADVANCE_8")
      (fields
        (field (name "MF") "Toshiba")
        (field (name "MPN") "TPH1R204PL")
        (field (name "MF_1") "Toshiba")
        (field (name "MPN_1") "TPH2R506PL,L1Q")
      )
      (libsource (lib "eagle-import") (part "TPH1R204PLSOP_ADVANCE_8"))
    )
    (comp (ref "Q5")
      (value "TPH1R204PLSOP_ADVANCE_8")
      (footprint "eagle-import:SOP_ADVANCE_8")
      (fields
        (field (name "MF") "Toshiba")
        (field (name "MPN") "TPH1R204PL")
        (field (name "MF_1") "Toshiba")
        (field (name "MPN_1") "TPH2R506PL,L1Q")
      )
      (libsource (lib "eagle-import") (part "TPH1R204PLSOP_ADVANCE_8"))
    )
    (comp (ref "Q6")
      (value "TPH1R204PLSOP_ADVANCE_8")
      (footprint "eagle-import:SOP_ADVANCE_8")
      (fields
        (field (name "MF") "Toshiba")
        (field (name "MPN") "TPH1R204PL")
        (field (name "MF_1") "Toshiba")
        (field (name "MPN_1") "TPH2R506PL,L1Q")
      )
      (libsource (lib "eagle-import") (part "TPH1R204PLSOP_ADVANCE_8"))
    )
    (comp (ref "R1")
      (value "560")
      (footprint "eagle-import:R0402")
      (fields (field (name "HOUSEPART") "1") (field (name "MPN") "MF-RES-0402-560"))
      (libsource (lib "eagle-import") (part "mfpassives_RESISTOR_0402"))
    )
    (comp (ref "R2")
      (value "560")
      (footprint "eagle-import:R0402")
      (fields (field (name "HOUSEPART") "1") (field (name "MPN") "MF-RES-0402-560"))
      (libsource (lib "eagle-import") (part "mfpassives_RESISTOR_0402"))
    )
    (comp (ref "R3")
      (value "2k")
      (footprint "eagle-import:R0402")
      (fields (field (name "HOUSEPART") "YES") (field (name "MPN") "MF-RES-0402-2K"))
      (libsource (lib "eagle-import") (part "mfpassives_RESISTOR_0402"))
    )
    (comp (ref "R4")
      (value "2k")
      (footprint "eagle-import:R0402")
      (fields (field (name "HOUSEPART") "YES") (field (name "MPN") "MF-RES-0402-2K"))
      (libsource (lib "eagle-import") (part "mfpassives_RESISTOR_0402"))
    )
    (comp (ref "R5")
      (value "100k 1%")
      (footprint "eagle-import:R0402")
      (fields (field (name "MF") "Yageo") (field (name "MPN") "RC0402FR-07100KL"))
      (libsource (lib "eagle-import") (part "mfpassives_RESISTOR_0402"))
    )
    (comp (ref "R6")
      (value "4.7k 1%")
      (footprint "eagle-import:R0402")
      (fields (field (name "MF") "Yageo") (field (name "MPN") "RC0402FR-074K7L"))
      (libsource (lib "eagle-import") (part "mfpassives_RESISTOR_0402"))
    )
    (comp (ref "R7")
      (value "10k 1%")
      (footprint "eagle-import:R0402")
      (fields (field (name "MF") "Yageo") (field (name "MPN") "RC0402FR-0710KL"))
      (libsource (lib "eagle-import") (part "mfpassives_RESISTOR_0402"))
    )
    (comp (ref "R8")
      (value "47k NTC")
      (footprint "eagle-import:R0402")
      (fields (field (name "MF") "Murata") (field (name "MPN") "NCP15WB473F03RC"))
      (libsource (lib "eagle-import") (part "mfpassives_RESISTOR_0402"))
    )
    (comp (ref "R9")
      (value "10k 1%")
      (footprint "eagle-import:R0402")
      (fields (field (name "MF") "Yageo") (field (name "MPN") "RC0402FR-0710KL"))
      (libsource (lib "eagle-import") (part "mfpassives_RESISTOR_0402"))
    )
    (comp (ref "R10")
      (value "DNP")
      (footprint "eagle-import:R0402")
      (fields (field (name "POPULATE") "0"))
      (libsource (lib "eagle-import") (part "mfpassives_RESISTOR_0402"))
    )
    (comp (ref "R13")
      (value "2k")
      (footprint "eagle-import:R0402")
      (fields (field (name "HOUSEPART") "YES") (field (name "MPN") "MF-RES-0402-2K"))
      (libsource (lib "eagle-import") (part "mfpassives_RESISTOR_0402"))
    )
    (comp (ref "R14")
      (value "2k")
      (footprint "eagle-import:R0402")
      (fields (field (name "HOUSEPART") "YES") (field (name "MPN") "MF-RES-0402-2K"))
      (libsource (lib "eagle-import") (part "mfpassives_RESISTOR_0402"))
    )
    (comp (ref "R15")
      (value "22")
      (footprint "eagle-import:R0402_NOBORDER")
      (fields (field (name "HOUSEPART") "1") (field (name "MPN") "MF-RES-0402-22"))
      (libsource (lib "eagle-import") (part "RESISTOR_0402_NOBORDER"))
    )
    (comp (ref "R16")
      (value "22")
      (footprint "eagle-import:R0402_NOBORDER")
      (fields (field (name "HOUSEPART") "1") (field (name "MPN") "MF-RES-0402-22"))
      (libsource (lib "eagle-import") (part "RESISTOR_0402_NOBORDER"))
    )
    (comp (ref "R17")
      (value "22")
      (footprint "eagle-import:R0402_NOBORDER")
      (fields (field (name "HOUSEPART") "1") (field (name "MPN") "MF-RES-0402-22"))
      (libsource (lib "eagle-import") (part "RESISTOR_0402_NOBORDER"))
    )
    (comp (ref "R22")
      (value "7.5")
      (footprint "eagle-import:R0402")
      (fields (field (name "HOUSEPART") "1") (field (name "MPN") "RC0402FR-077R5L"))
      (libsource (lib "eagle-import") (part "mfpassives_RESISTOR_0402"))
    )
    (comp (ref "R23")
      (value "7.5")
      (footprint "eagle-import:R0402")
      (fields (field (name "HOUSEPART") "1") (field (name "MPN") "RC0402FR-077R5L"))
      (libsource (lib "eagle-import") (part "mfpassives_RESISTOR_0402"))
    )
    (comp (ref "R24")
      (value "7.5")
      (footprint "eagle-import:R0402")
      (fields (field (name "HOUSEPART") "1") (field (name "MPN") "RC0402FR-077R5L"))
      (libsource (lib "eagle-import") (part "mfpassives_RESISTOR_0402"))
    )
    (comp (ref "R25")
      (value "7.5")
      (footprint "eagle-import:R0402")
      (fields (field (name "HOUSEPART") "1") (field (name "MPN") "RC0402FR-077R5L"))
      (libsource (lib "eagle-import") (part "mfpassives_RESISTOR_0402"))
    )
    (comp (ref "R26")
      (value "7.5")
      (footprint "eagle-import:R0402")
      (fields (field (name "HOUSEPART") "1") (field (name "MPN") "RC0402FR-077R5L"))
      (libsource (lib "eagle-import") (part "mfpassives_RESISTOR_0402"))
    )
    (comp (ref "R27")
      (value "7.5")
      (footprint "eagle-import:R0402")
      (fields (field (name "HOUSEPART") "1") (field (name "MPN") "RC0402FR-077R5L"))
      (libsource (lib "eagle-import") (part "mfpassives_RESISTOR_0402"))
    )
    (comp (ref "RA")
      (value "0.5mOhm 1% 2W")
      (footprint "eagle-import:M1206")
      (fields (field (name "MF") "Stackpole Electronics") (field (name "MPN") "HCS1206FTL500"))
      (libsource (lib "eagle-import") (part "R-US_M1206"))
    )
    (comp (ref "RB")
      (value "0.5mOhm 1% 2W")
      (footprint "eagle-import:M1206")
      (fields (field (name "MF") "Stackpole Electronics") (field (name "MPN") "HCS1206FTL500"))
      (libsource (lib "eagle-import") (part "R-US_M1206"))
    )
    (comp (ref "RC")
      (value "0.5mOhm 1% 2W")
      (footprint "eagle-import:M1206")
      (fields (field (name "MF") "Stackpole Electronics") (field (name "MPN") "HCS1206FTL500"))
      (libsource (lib "eagle-import") (part "R-US_M1206"))
    )
    (comp (ref "SH1")
      (value "SHORTT5")
      (footprint "eagle-import:SHORT_TOP-50")
      (libsource (lib "eagle-import") (part "SHORTT5"))
    )
    (comp (ref "SH2")
      (value "SHORTT5")
      (footprint "eagle-import:SHORT_TOP-50")
      (libsource (lib "eagle-import") (part "SHORTT5"))
    )
    (comp (ref "SH3")
      (value "SHORTT5")
      (footprint "eagle-import:SHORT_TOP-50")
      (libsource (lib "eagle-import") (part "SHORTT5"))
    )
    (comp (ref "SH4")
      (value "SHORTMEDIUM")
      (footprint "eagle-import:SHORT_TOP-MEDIUM")
      (libsource (lib "eagle-import") (part "SHORTMEDIUM"))
    )
    (comp (ref "SWD")
      (value "JST-ZH6")
      (footprint "eagle-import:JST_S6B-ZR-SM4A-TF(LF)(SN)")
      (fields (field (name "MF") "JST") (field (name "MPN") "S6B-ZR-SM4A-TF(LF)(SN)"))
      (libsource (lib "eagle-import") (part "JST-ZH6"))
    )
    (comp (ref "TEMP1")
      (value "PAD24AWG_PAD")
      (footprint "eagle-import:24AWG_PAD")
      (libsource (lib "eagle-import") (part "PAD24AWG_PAD"))
    )
    (comp (ref "TEMP2")
      (value "PAD24AWG_PAD")
      (footprint "eagle-import:24AWG_PAD")
      (libsource (lib "eagle-import") (part "PAD24AWG_PAD"))
    )
    (comp (ref "U1")
      (value "STM32G474CEU6")
      (footprint "eagle-import:QFN50P700X700X60-49N")
      (fields (field (name "MOUSER_PART_NUMBER") "511-STM32G474CEU6"))
      (libsource (lib "eagle-import") (part "STM32G474CEU6"))
    )
    (comp (ref "U2")
      (value "TCAN334G")
      (footprint "eagle-import:SOIC8")
      (fields (field (name "MF") "TI") (field (name "MPN") "TCAN337GDR"))
      (libsource (lib "eagle-import") (part "TCAN334G"))
    )
    (comp (ref "U3")
      (value "AS5147")
      (footprint "eagle-import:TSSOP14")
      (fields (field (name "MF") "AMS") (field (name "MPN") "AS5047P-ATSM"))
      (libsource (lib "eagle-import") (part "AS5147"))
    )
    (comp (ref "U4")
      (value "MAX15062AATA+T")
      (footprint "eagle-import:21-0487A_MXM")
      (fields (field (name "COPYRIGHT") "Copyright (C) 2018 Accelerated Designs. All rights reserved"))
      (libsource (lib "eagle-import") (part "MAX15062AATA+T"))
    )
    (comp (ref "U5")
      (value "DRV8353S")
      (footprint "eagle-import:WQFN-40")
      (fields (field (name "MF") "TI") (field (name "MPN") "DRV8353FSRTAR"))
      (libsource (lib "eagle-import") (part "DRV8353S"))
    )
    (comp (ref "U6")
      (value "TCAN334GSOT23")
      (footprint "eagle-import:SOT23-8")
      (fields (field (name "MF") "TI") (field (name "MPN") "TCAN334GDCNT"))
      (libsource (lib "eagle-import") (part "TCAN334GSOT23"))
    )
  )
  (nets
    (net (code "1") (name "+3V3") (class "Default")
      (node (ref "ABS") (pin "1") (pinfunction "1_1") (pintype "passive"))
      (node (ref "C1") (pin "P$1") (pinfunction "P$1_P$1") (pintype "passive"))
      (node (ref "C10") (pin "P$1") (pinfunction "P$1_P$1") (pintype "passive"))
      (node (ref "C11") (pin "P$1") (pinfunction "P$1_P$1") (pintype "passive"))
      (node (ref "C12") (pin "P$1") (pinfunction "P$1_P$1") (pintype "passive"))
      (node (ref "C18") (pin "P$2") (pinfunction "P$2_P$2") (pintype "passive"))
      (node (ref "C2") (pin "P$1") (pinfunction "P$1_P$1") (pintype "passive"))
      (node (ref "C21") (pin "P$1") (pinfunction "P$1_P$1") (pintype "passive"))
      (node (ref "C4") (pin "P$1") (pinfunction "P$1_P$1") (pintype "passive"))
      (node (ref "C5") (pin "P$1") (pinfunction "P$1_P$1") (pintype "passive"))
      (node (ref "C56") (pin "P$1") (pinfunction "P$1_P$1") (pintype "passive"))
      (node (ref "C6") (pin "P$1") (pinfunction "P$1_P$1") (pintype "passive"))
      (node (ref "C7") (pin "P$2") (pinfunction "P$2_P$2") (pintype "passive"))
      (node (ref "C8") (pin "P$1") (pinfunction "P$1_P$1") (pintype "passive"))
      (node (ref "C9") (pin "P$1") (pinfunction "P$1_P$1") (pintype "passive"))
      (node (ref "D33") (pin "P$1") (pinfunction "P$1_P$1") (pintype "bidirectional"))
      (node (ref "ENC") (pin "1") (pinfunction "1_1") (pintype "passive"))
      (node (ref "L1") (pin "1") (pinfunction "1_1") (pintype "passive"))
      (node (ref "R1") (pin "P$1") (pinfunction "P$1_P$1") (pintype "passive"))
      (node (ref "R13") (pin "P$1") (pinfunction "P$1_P$1") (pintype "passive"))
      (node (ref "R14") (pin "P$1") (pinfunction "P$1_P$1") (pintype "passive"))
      (node (ref "R2") (pin "P$1") (pinfunction "P$1_P$1") (pintype "passive"))
      (node (ref "R3") (pin "P$1") (pinfunction "P$1_P$1") (pintype "passive"))
      (node (ref "R4") (pin "P$1") (pinfunction "P$1_P$1") (pintype "passive"))
      (node (ref "R8") (pin "P$1") (pinfunction "P$1_P$1") (pintype "passive"))
      (node (ref "SWD") (pin "6") (pinfunction "6_6") (pintype "passive"))
      (node (ref "TEMP1") (pin "P$1") (pinfunction "P$1_P$1") (pintype "bidirectional"))
      (node (ref "U1") (pin "1") (pinfunction "VBAT_1") (pintype "bidirectional"))
      (node (ref "U1") (pin "20") (pinfunction "VREF+_20") (pintype "bidirectional"))
      (node (ref "U1") (pin "21") (pinfunction "VDDA_21") (pintype "bidirectional"))
      (node (ref "U1") (pin "23") (pinfunction "VDD_1_23") (pintype "bidirectional"))
      (node (ref "U1") (pin "35") (pinfunction "VDD_2_35") (pintype "bidirectional"))
      (node (ref "U1") (pin "48") (pinfunction "VDD_3_48") (pintype "bidirectional"))
      (node (ref "U2") (pin "3") (pinfunction "VCC_3") (pintype "power_in"))
      (node (ref "U3") (pin "12") (pinfunction "VDD3V_12") (pintype "bidirectional"))
      (node (ref "U4") (pin "4") (pinfunction "FB/VOUT_4") (pintype "bidirectional"))
      (node (ref "U5") (pin "24") (pinfunction "VREF_24") (pintype "bidirectional"))
      (node (ref "U6") (pin "3") (pinfunction "VCC_3") (pintype "power_in"))
    )
    (net (code "2") (name "/AS5047_A") (class "Default")
      (node (ref "U1") (pin "43") (pinfunction "PB5_43") (pintype "bidirectional"))
      (node (ref "U3") (pin "7") (pinfunction "A_7") (pintype "bidirectional"))
    )
    (net (code "3") (name "/AS5047_B") (class "Default")
      (node (ref "U1") (pin "42") (pinfunction "PB4_42") (pintype "bidirectional"))
      (node (ref "U3") (pin "6") (pinfunction "B_6") (pintype "bidirectional"))
    )
    (net (code "4") (name "/AS5047_CS") (class "Default")
      (node (ref "U1") (pin "24") (pinfunction "PB11_24") (pintype "bidirectional"))
      (node (ref "U3") (pin "1") (pinfunction "CS/_1") (pintype "bidirectional"))
    )
    (net (code "5") (name "/AS5047_MISO") (class "Default")
      (node (ref "ENC") (pin "5") (pinfunction "5_5") (pintype "passive"))
      (node (ref "U1") (pin "27") (pinfunction "PB14_27") (pintype "bidirectional"))
      (node (ref "U3") (pin "3") (pinfunction "MISO_3") (pintype "bidirectional"))
    )
    (net (code "6") (name "/AS5047_MOSI") (class "Default")
      (node (ref "ENC") (pin "6") (pinfunction "6_6") (pintype "passive"))
      (node (ref "U1") (pin "28") (pinfunction "PB15_28") (pintype "bidirectional"))
      (node (ref "U3") (pin "4") (pinfunction "MOSI_4") (pintype "bidirectional"))
    )
    (net (code "7") (name "/AS5047_SCK") (class "Default")
      (node (ref "ENC") (pin "4") (pinfunction "4_4") (pintype "passive"))
      (node (ref "U1") (pin "26") (pinfunction "PB13_26") (pintype "bidirectional"))
      (node (ref "U3") (pin "2") (pinfunction "CLK_2") (pintype "bidirectional"))
    )
    (net (code "8") (name "/CAN2_N") (class "Default")
      (node (ref "L2") (pin "P$2") (pinfunction "2_P$2") (pintype "passive"))
      (node (ref "U2") (pin "6") (pinfunction "CANL_6") (pintype "bidirectional"))
      (node (ref "U6") (pin "6") (pinfunction "CANL_6") (pintype "bidirectional"))
    )
    (net (code "9") (name "/CAN2_P") (class "Default")
      (node (ref "L3") (pin "P$2") (pinfunction "2_P$2") (pintype "passive"))
      (node (ref "U2") (pin "7") (pinfunction "CANH_7") (pintype "bidirectional"))
      (node (ref "U6") (pin "7") (pinfunction "CANH_7") (pintype "bidirectional"))
    )
    (net (code "10") (name "/CAN_N") (class "Default")
      (node (ref "CAN1") (pin "2") (pinfunction "2_2") (pintype "passive"))
      (node (ref "CAN2") (pin "2") (pinfunction "2_2") (pintype "passive"))
      (node (ref "D4") (pin "2") (pinfunction "2_2") (pintype "bidirectional"))
      (node (ref "L2") (pin "P$1") (pinfunction "1_P$1") (pintype "passive"))
    )
    (net (code "11") (name "/CAN_P") (class "Default")
      (node (ref "CAN1") (pin "1") (pinfunction "1_1") (pintype "passive"))
      (node (ref "CAN2") (pin "1") (pinfunction "1_1") (pintype "passive"))
      (node (ref "D4") (pin "1") (pinfunction "1_1") (pintype "bidirectional"))
      (node (ref "L3") (pin "P$1") (pinfunction "1_P$1") (pintype "passive"))
    )
    (net (code "12") (name "/CAN_RX") (class "Default")
      (node (ref "U1") (pin "33") (pinfunction "PA11_33") (pintype "bidirectional"))
      (node (ref "U2") (pin "4") (pinfunction "RXD_4") (pintype "output"))
      (node (ref "U6") (pin "4") (pinfunction "RXD_4") (pintype "output"))
    )
    (net (code "13") (name "/CAN_TX") (class "Default")
      (node (ref "U1") (pin "34") (pinfunction "PA12_34") (pintype "bidirectional"))
      (node (ref "U2") (pin "1") (pinfunction "TXD_1") (pintype "input"))
      (node (ref "U6") (pin "1") (pinfunction "TXD_1") (pintype "input"))
    )
    (net (code "14") (name "/CUR1") (class "Default")
      (node (ref "R15") (pin "P$1") (pinfunction "P$1_P$1") (pintype "passive"))
      (node (ref "U5") (pin "23") (pinfunction "SOA_23") (pintype "bidirectional"))
    )
    (net (code "15") (name "/CUR2") (class "Default")
      (node (ref "R16") (pin "P$1") (pinfunction "P$1_P$1") (pintype "passive"))
      (node (ref "U5") (pin "22") (pinfunction "SOB_22") (pintype "bidirectional"))
    )
    (net (code "16") (name "/CUR3") (class "Default")
      (node (ref "R17") (pin "P$1") (pinfunction "P$1_P$1") (pintype "passive"))
      (node (ref "U5") (pin "21") (pinfunction "SOC_21") (pintype "bidirectional"))
    )
    (net (code "17") (name "/DAC") (class "Default")
      (node (ref "DAC") (pin "P$1") (pinfunction "P$1_P$1") (pintype "bidirectional"))
      (node (ref "U1") (pin "12") (pinfunction "PA4_12") (pintype "bidirectional"))
    )
    (net (code "18") (name "/DEBUG1") (class "Default")
      (node (ref "DBG1") (pin "P$1") (pinfunction "P$1_P$1") (pintype "bidirectional"))
      (node (ref "U1") (pin "3") (pinfunction "PC14-OSC32_IN_3") (pintype "bidirectional"))
    )
    (net (code "19") (name "/DEBUG2") (class "Default")
      (node (ref "DBG2") (pin "P$1") (pinfunction "P$1_P$1") (pintype "bidirectional"))
      (node (ref "U1") (pin "4") (pinfunction "PC15-OSC32_OUT_4") (pintype "bidirectional"))
    )
    (net (code "20") (name "/DEBUG_RX") (class "Default")
      (node (ref "DTR") (pin "P$1") (pinfunction "P$1_P$1") (pintype "bidirectional"))
      (node (ref "U1") (pin "40") (pinfunction "PC11_40") (pintype "bidirectional"))
    )
    (net (code "21") (name "/DEBUG_TX") (class "Default")
      (node (ref "DTX") (pin "P$1") (pinfunction "P$1_P$1") (pintype "bidirectional"))
      (node (ref "U1") (pin "39") (pinfunction "PC10_39") (pintype "bidirectional"))
    )
    (net (code "22") (name "/DRV8323_CS") (class "Default")
      (node (ref "DRV_CS") (pin "P$1") (pinfunction "P$1_P$1") (pintype "bidirectional"))
      (node (ref "U1") (pin "16") (pinfunction "PC4_16") (pintype "bidirectional"))
      (node (ref "U5") (pin "30") (pinfunction "CS_30") (pintype "bidirectional"))
    )
    (net (code "23") (name "/DRV8323_MISO") (class "Default")
      (node (ref "DRV_MISO") (pin "P$1") (pinfunction "P$1_P$1") (pintype "bidirectional"))
      (node (ref "R13") (pin "P$2") (pinfunction "P$2_P$2") (pintype "passive"))
      (node (ref "U1") (pin "14") (pinfunction "PA6_14") (pintype "bidirectional"))
      (node (ref "U5") (pin "27") (pinfunction "MISO_27") (pintype "bidirectional"))
    )
    (net (code "24") (name "/DRV8323_MOSI") (class "Default")
      (node (ref "DRV_MOSI") (pin "P$1") (pinfunction "P$1_P$1") (pintype "bidirectional"))
      (node (ref "U1") (pin "15") (pinfunction "PA7_15") (pintype "bidirectional"))
      (node (ref "U5") (pin "28") (pinfunction "MOSI_28") (pintype "bidirectional"))
    )
    (net (code "25") (name "/DRV8323_SCLK") (class "Default")
      (node (ref "DRV_SCK") (pin "P$1") (pinfunction "P$1_P$1") (pintype "bidirectional"))
      (node (ref "U1") (pin "13") (pinfunction "PA5_13") (pintype "bidirectional"))
      (node (ref "U5") (pin "29") (pinfunction "SCLK_29") (pintype "bidirectional"))
    )
    (net (code "26") (name "/FCUR1") (class "Default")
      (node (ref "C58") (pin "P$1") (pinfunction "P$1_P$1") (pintype "passive"))
      (node (ref "R15") (pin "P$2") (pinfunction "P$2_P$2") (pintype "passive"))
      (node (ref "U1") (pin "17") (pinfunction "PB0_17") (pintype "bidirectional"))
    )
    (net (code "27") (name "/FCUR2") (class "Default")
      (node (ref "C59") (pin "P$1") (pinfunction "P$1_P$1") (pintype "passive"))
      (node (ref "R16") (pin "P$2") (pinfunction "P$2_P$2") (pintype "passive"))
      (node (ref "U1") (pin "18") (pinfunction "PB1_18") (pintype "bidirectional"))
    )
    (net (code "28") (name "/FCUR3") (class "Default")
      (node (ref "C60") (pin "P$1") (pinfunction "P$1_P$1") (pintype "passive"))
      (node (ref "R17") (pin "P$2") (pinfunction "P$2_P$2") (pintype "passive"))
      (node (ref "U1") (pin "19") (pinfunction "PB2_19") (pintype "bidirectional"))
    )
    (net (code "29") (name "/GHA") (class "Default")
      (node (ref "D10") (pin "1") (pinfunction "K_1") (pintype "bidirectional"))
      (node (ref "R22") (pin "P$1") (pinfunction "P$1_P$1") (pintype "passive"))
      (node (ref "U5") (pin "6") (pinfunction "GHA_6") (pintype "bidirectional"))
    )
    (net (code "30") (name "/GHA_D") (class "Default")
      (node (ref "D10") (pin "2") (pinfunction "A_2") (pintype "bidirectional"))
      (node (ref "Q1") (pin "4") (pinfunction "G_4") (pintype "passive"))
      (node (ref "R22") (pin "P$2") (pinfunction "P$2_P$2") (pintype "passive"))
    )
    (net (code "31") (name "/GHB") (class "Default")
      (node (ref "D11") (pin "1") (pinfunction "K_1") (pintype "bidirectional"))
      (node (ref "R24") (pin "P$1") (pinfunction "P$1_P$1") (pintype "passive"))
      (node (ref "U5") (pin "15") (pinfunction "GHB_15") (pintype "bidirectional"))
    )
    (net (code "32") (name "/GHB_D") (class "Default")
      (node (ref "D11") (pin "2") (pinfunction "A_2") (pintype "bidirectional"))
      (node (ref "Q3") (pin "4") (pinfunction "G_4") (pintype "passive"))
      (node (ref "R24") (pin "P$2") (pinfunction "P$2_P$2") (pintype "passive"))
    )
    (net (code "33") (name "/GHC") (class "Default")
      (node (ref "D12") (pin "1") (pinfunction "K_1") (pintype "bidirectional"))
      (node (ref "R26") (pin "P$1") (pinfunction "P$1_P$1") (pintype "passive"))
      (node (ref "U5") (pin "16") (pinfunction "GHC_16") (pintype "bidirectional"))
    )
    (net (code "34") (name "/GHC_D") (class "Default")
      (node (ref "D12") (pin "2") (pinfunction "A_2") (pintype "bidirectional"))
      (node (ref "Q5") (pin "4") (pinfunction "G_4") (pintype "passive"))
      (node (ref "R26") (pin "P$2") (pinfunction "P$2_P$2") (pintype "passive"))
    )
    (net (code "35") (name "/GLA") (class "Default")
      (node (ref "D7") (pin "1") (pinfunction "K_1") (pintype "bidirectional"))
      (node (ref "R23") (pin "P$1") (pinfunction "P$1_P$1") (pintype "passive"))
      (node (ref "U5") (pin "8") (pinfunction "GLA_8") (pintype "bidirectional"))
    )
    (net (code "36") (name "/GLA_D") (class "Default")
      (node (ref "D1") (pin "1") (pinfunction "K_1") (pintype "bidirectional"))
      (node (ref "D7") (pin "2") (pinfunction "A_2") (pintype "bidirectional"))
      (node (ref "Q2") (pin "4") (pinfunction "G_4") (pintype "passive"))
      (node (ref "R23") (pin "P$2") (pinfunction "P$2_P$2") (pintype "passive"))
    )
    (net (code "37") (name "/GLB") (class "Default")
      (node (ref "D8") (pin "1") (pinfunction "K_1") (pintype "bidirectional"))
      (node (ref "R25") (pin "P$1") (pinfunction "P$1_P$1") (pintype "passive"))
      (node (ref "U5") (pin "13") (pinfunction "GLB_13") (pintype "bidirectional"))
    )
    (net (code "38") (name "/GLB_D") (class "Default")
      (node (ref "D5") (pin "1") (pinfunction "K_1") (pintype "bidirectional"))
      (node (ref "D8") (pin "2") (pinfunction "A_2") (pintype "bidirectional"))
      (node (ref "Q4") (pin "4") (pinfunction "G_4") (pintype "passive"))
      (node (ref "R25") (pin "P$2") (pinfunction "P$2_P$2") (pintype "passive"))
    )
    (net (code "39") (name "/GLC") (class "Default")
      (node (ref "D9") (pin "1") (pinfunction "K_1") (pintype "bidirectional"))
      (node (ref "R27") (pin "P$1") (pinfunction "P$1_P$1") (pintype "passive"))
      (node (ref "U5") (pin "18") (pinfunction "GLC_18") (pintype "bidirectional"))
    )
    (net (code "40") (name "/GLC_D") (class "Default")
      (node (ref "D6") (pin "1") (pinfunction "K_1") (pintype "bidirectional"))
      (node (ref "D9") (pin "2") (pinfunction "A_2") (pintype "bidirectional"))
      (node (ref "Q6") (pin "4") (pinfunction "G_4") (pintype "passive"))
      (node (ref "R27") (pin "P$2") (pinfunction "P$2_P$2") (pintype "passive"))
    )
    (net (code "41") (name "/I2C_ABS_SCL") (class "Default")
      (node (ref "ABS") (pin "2") (pinfunction "2_2") (pintype "passive"))
      (node (ref "R4") (pin "P$2") (pinfunction "P$2_P$2") (pintype "passive"))
      (node (ref "U1") (pin "46") (pinfunction "PB8-BOOT0_46") (pintype "bidirectional"))
    )
    (net (code "42") (name "/I2C_ABS_SDA") (class "Default")
      (node (ref "ABS") (pin "3") (pinfunction "3_3") (pintype "passive"))
      (node (ref "R3") (pin "P$2") (pinfunction "P$2_P$2") (pintype "passive"))
      (node (ref "U1") (pin "47") (pinfunction "PB9_47") (pintype "bidirectional"))
    )
    (net (code "43") (name "/LED1") (class "Default")
      (node (ref "D3") (pin "CATHODE") (pinfunction "CATHODE_CATHODE") (pintype "power_in"))
      (node (ref "U1") (pin "5") (pinfunction "PF0-OSC_IN_5") (pintype "bidirectional"))
    )
    (net (code "44") (name "/LED2") (class "Default")
      (node (ref "D2") (pin "CATHODE") (pinfunction "CATHODE_CATHODE") (pintype "power_in"))
      (node (ref "U1") (pin "6") (pinfunction "PF1-OSC_OUT_6") (pintype "bidirectional"))
    )
    (net (code "45") (name "/MOTOR1") (class "Default")
      (node (ref "MOT1") (pin "P$1") (pinfunction "P$1_P$1") (pintype "bidirectional"))
      (node (ref "U1") (pin "8") (pinfunction "PA0_8") (pintype "bidirectional"))
      (node (ref "U5") (pin "32") (pinfunction "INHA_32") (pintype "bidirectional"))
    )
    (net (code "46") (name "/MOTOR2") (class "Default")
      (node (ref "MOT2") (pin "P$1") (pinfunction "P$1_P$1") (pintype "bidirectional"))
      (node (ref "U1") (pin "9") (pinfunction "PA1_9") (pintype "bidirectional"))
      (node (ref "U5") (pin "34") (pinfunction "INHB_34") (pintype "bidirectional"))
    )
    (net (code "47") (name "/MOTOR3") (class "Default")
      (node (ref "MOT3") (pin "P$1") (pinfunction "P$1_P$1") (pintype "bidirectional"))
      (node (ref "U1") (pin "10") (pinfunction "PA2_10") (pintype "bidirectional"))
      (node (ref "U5") (pin "36") (pinfunction "INHC_36") (pintype "bidirectional"))
    )
    (net (code "48") (name "/MOTOR_ENABLE") (class "Default")
      (node (ref "U1") (pin "11") (pinfunction "PA3_11") (pintype "bidirectional"))
      (node (ref "U5") (pin "31") (pinfunction "ENABLE_31") (pintype "bidirectional"))
    )
    (net (code "49") (name "/MOTOR_FAULT") (class "Default")
      (node (ref "R14") (pin "P$2") (pinfunction "P$2_P$2") (pintype "passive"))
      (node (ref "U1") (pin "44") (pinfunction "PB6_44") (pintype "bidirectional"))
      (node (ref "U5") (pin "26") (pinfunction "FAULT_26") (pintype "bidirectional"))
    )
    (net (code "50") (name "/MOTOR_HIZ") (class "Default")
      (node (ref "U1") (pin "45") (pinfunction "PB7_45") (pintype "bidirectional"))
      (node (ref "U5") (pin "33") (pinfunction "INLA_33") (pintype "bidirectional"))
      (node (ref "U5") (pin "35") (pinfunction "INLB_35") (pintype "bidirectional"))
      (node (ref "U5") (pin "37") (pinfunction "INLC_37") (pintype "bidirectional"))
    )
    (net (code "51") (name "/NRST") (class "Default")
      (node (ref "C3") (pin "P$1") (pinfunction "P$1_P$1") (pintype "passive"))
      (node (ref "SWD") (pin "2") (pinfunction "2_2") (pintype "passive"))
      (node (ref "U1") (pin "7") (pinfunction "PG10-NRST_7") (pintype "bidirectional"))
    )
    (net (code "52") (name "/SECONDARY_ENC_CS") (class "Default")
      (node (ref "ENC") (pin "2") (pinfunction "2_2") (pintype "passive"))
      (node (ref "U1") (pin "2") (pinfunction "PC13_2") (pintype "bidirectional"))
    )
    (net (code "53") (name "/SHA") (class "Default")
      (node (ref "A") (pin "1") (pinfunction "P$1_1") (pintype "bidirectional"))
      (node (ref "DA") (pin "P$1") (pinfunction "P$1_P$1") (pintype "bidirectional"))
      (node (ref "Q1") (pin "1") (pinfunction "S_1") (pintype "passive"))
      (node (ref "Q1") (pin "2") (pinfunction "S_2") (pintype "passive"))
      (node (ref "Q1") (pin "3") (pinfunction "S_3") (pintype "passive"))
      (node (ref "Q2") (pin "5") (pinfunction "D_5") (pintype "passive"))
      (node (ref "Q2") (pin "6") (pinfunction "D_6") (pintype "passive"))
      (node (ref "Q2") (pin "7") (pinfunction "D_7") (pintype "passive"))
      (node (ref "Q2") (pin "8") (pinfunction "D_8") (pintype "passive"))
      (node (ref "Q2") (pin "PAD") (pinfunction "D_PAD") (pintype "passive"))
      (node (ref "U5") (pin "7") (pinfunction "SHA_7") (pintype "bidirectional"))
    )
    (net (code "54") (name "/SHB") (class "Default")
      (node (ref "B") (pin "1") (pinfunction "P$1_1") (pintype "bidirectional"))
      (node (ref "DB") (pin "P$1") (pinfunction "P$1_P$1") (pintype "bidirectional"))
      (node (ref "Q3") (pin "1") (pinfunction "S_1") (pintype "passive"))
      (node (ref "Q3") (pin "2") (pinfunction "S_2") (pintype "passive"))
      (node (ref "Q3") (pin "3") (pinfunction "S_3") (pintype "passive"))
      (node (ref "Q4") (pin "5") (pinfunction "D_5") (pintype "passive"))
      (node (ref "Q4") (pin "6") (pinfunction "D_6") (pintype "passive"))
      (node (ref "Q4") (pin "7") (pinfunction "D_7") (pintype "passive"))
      (node (ref "Q4") (pin "8") (pinfunction "D_8") (pintype "passive"))
      (node (ref "Q4") (pin "PAD") (pinfunction "D_PAD") (pintype "passive"))
      (node (ref "U5") (pin "14") (pinfunction "SHB_14") (pintype "bidirectional"))
    )
    (net (code "55") (name "/SHC") (class "Default")
      (node (ref "C") (pin "1") (pinfunction "P$1_1") (pintype "bidirectional"))
      (node (ref "DC") (pin "P$1") (pinfunction "P$1_P$1") (pintype "bidirectional"))
      (node (ref "Q5") (pin "1") (pinfunction "S_1") (pintype "passive"))
      (node (ref "Q5") (pin "2") (pinfunction "S_2") (pintype "passive"))
      (node (ref "Q5") (pin "3") (pinfunction "S_3") (pintype "passive"))
      (node (ref "Q6") (pin "5") (pinfunction "D_5") (pintype "passive"))
      (node (ref "Q6") (pin "6") (pinfunction "D_6") (pintype "passive"))
      (node (ref "Q6") (pin "7") (pinfunction "D_7") (pintype "passive"))
      (node (ref "Q6") (pin "8") (pinfunction "D_8") (pintype "passive"))
      (node (ref "Q6") (pin "PAD") (pinfunction "D_PAD") (pintype "passive"))
      (node (ref "U5") (pin "17") (pinfunction "SHC_17") (pintype "bidirectional"))
    )
    (net (code "56") (name "/SWCLK") (class "Default")
      (node (ref "SWD") (pin "5") (pinfunction "5_5") (pintype "passive"))
      (node (ref "U1") (pin "37") (pinfunction "PA14_37") (pintype "bidirectional"))
    )
    (net (code "57") (name "/SWDIO") (class "Default")
      (node (ref "SWD") (pin "3") (pinfunction "3_3") (pintype "passive"))
      (node (ref "U1") (pin "36") (pinfunction "PA13_36") (pintype "bidirectional"))
    )
    (net (code "58") (name "/SXA_N") (class "Default")
      (node (ref "SH1") (pin "1") (pinfunction "P$1_1") (pintype "bidirectional"))
      (node (ref "U5") (pin "10") (pinfunction "SNA_10") (pintype "bidirectional"))
    )
    (net (code "59") (name "/SXA_P") (class "Default")
      (node (ref "C61") (pin "P$2") (pinfunction "P$2_P$2") (pintype "passive"))
      (node (ref "Q2") (pin "1") (pinfunction "S_1") (pintype "passive"))
      (node (ref "Q2") (pin "2") (pinfunction "S_2") (pintype "passive"))
      (node (ref "Q2") (pin "3") (pinfunction "S_3") (pintype "passive"))
      (node (ref "RA") (pin "2") (pinfunction "2_2") (pintype "passive"))
      (node (ref "U5") (pin "9") (pinfunction "SPA_9") (pintype "bidirectional"))
    )
    (net (code "60") (name "/SXB_N") (class "Default")
      (node (ref "SH2") (pin "1") (pinfunction "P$1_1") (pintype "bidirectional"))
      (node (ref "U5") (pin "11") (pinfunction "SNB_11") (pintype "bidirectional"))
    )
    (net (code "61") (name "/SXB_P") (class "Default")
      (node (ref "C62") (pin "P$2") (pinfunction "P$2_P$2") (pintype "passive"))
      (node (ref "Q4") (pin "1") (pinfunction "S_1") (pintype "passive"))
      (node (ref "Q4") (pin "2") (pinfunction "S_2") (pintype "passive"))
      (node (ref "Q4") (pin "3") (pinfunction "S_3") (pintype "passive"))
      (node (ref "RB") (pin "2") (pinfunction "2_2") (pintype "passive"))
      (node (ref "U5") (pin "12") (pinfunction "SPB_12") (pintype "bidirectional"))
    )
    (net (code "62") (name "/SXC_N") (class "Default")
      (node (ref "SH3") (pin "1") (pinfunction "P$1_1") (pintype "bidirectional"))
      (node (ref "U5") (pin "20") (pinfunction "SNC_20") (pintype "bidirectional"))
    )
    (net (code "63") (name "/SXC_P") (class "Default")
      (node (ref "C63") (pin "P$2") (pinfunction "P$2_P$2") (pintype "passive"))
      (node (ref "Q6") (pin "1") (pinfunction "S_1") (pintype "passive"))
      (node (ref "Q6") (pin "2") (pinfunction "S_2") (pintype "passive"))
      (node (ref "Q6") (pin "3") (pinfunction "S_3") (pintype "passive"))
      (node (ref "RC") (pin "2") (pinfunction "2_2") (pintype "passive"))
      (node (ref "U5") (pin "19") (pinfunction "SPC_19") (pintype "bidirectional"))
    )
    (net (code "64") (name "/VBAT_SENSE") (class "Default")
      (node (ref "C57") (pin "P$1") (pinfunction "P$1_P$1") (pintype "passive"))
      (node (ref "R5") (pin "P$1") (pinfunction "P$1_P$1") (pintype "passive"))
      (node (ref "R6") (pin "P$2") (pinfunction "P$2_P$2") (pintype "passive"))
      (node (ref "U1") (pin "25") (pinfunction "PB12_25") (pintype "bidirectional"))
    )
    (net (code "65") (name "/VSW") (class "Default")
      (node (ref "L1") (pin "2") (pinfunction "2_2") (pintype "passive"))
      (node (ref "U4") (pin "8") (pinfunction "LX_8") (pintype "passive"))
    )
    (net (code "66") (name "/VTEMP_FET") (class "Default")
      (node (ref "C13") (pin "P$1") (pinfunction "P$1_P$1") (pintype "passive"))
      (node (ref "R8") (pin "P$2") (pinfunction "P$2_P$2") (pintype "passive"))
      (node (ref "R9") (pin "P$1") (pinfunction "P$1_P$1") (pintype "passive"))
      (node (ref "U1") (pin "31") (pinfunction "PA9_31") (pintype "bidirectional"))
    )
    (net (code "67") (name "/VTEMP_MOT") (class "Default")
      (node (ref "R7") (pin "P$1") (pinfunction "P$1_P$1") (pintype "passive"))
      (node (ref "TEMP2") (pin "P$1") (pinfunction "P$1_P$1") (pintype "bidirectional"))
      (node (ref "U1") (pin "30") (pinfunction "PA8_30") (pintype "bidirectional"))
    )
    (net (code "68") (name "GND") (class "Default")
      (node (ref "ABS") (pin "4") (pinfunction "4_4") (pintype "passive"))
      (node (ref "C1") (pin "P$2") (pinfunction "P$2_P$2") (pintype "passive"))
      (node (ref "C10") (pin "P$2") (pinfunction "P$2_P$2") (pintype "passive"))
      (node (ref "C11") (pin "P$2") (pinfunction "P$2_P$2") (pintype "passive"))
      (node (ref "C12") (pin "P$2") (pinfunction "P$2_P$2") (pintype "passive"))
      (node (ref "C13") (pin "P$2") (pinfunction "P$2_P$2") (pintype "passive"))
      (node (ref "C18") (pin "P$1") (pinfunction "P$1_P$1") (pintype "passive"))
      (node (ref "C2") (pin "P$2") (pinfunction "P$2_P$2") (pintype "passive"))
      (node (ref "C20") (pin "P$2") (pinfunction "P$2_P$2") (pintype "passive"))
      (node (ref "C21") (pin "P$2") (pinfunction "P$2_P$2") (pintype "passive"))
      (node (ref "C3") (pin "P$2") (pinfunction "P$2_P$2") (pintype "passive"))
      (node (ref "C4") (pin "P$2") (pinfunction "P$2_P$2") (pintype "passive"))
      (node (ref "C5") (pin "P$2") (pinfunction "P$2_P$2") (pintype "passive"))
      (node (ref "C56") (pin "P$2") (pinfunction "P$2_P$2") (pintype "passive"))
      (node (ref "C57") (pin "P$2") (pinfunction "P$2_P$2") (pintype "passive"))
      (node (ref "C58") (pin "P$2") (pinfunction "P$2_P$2") (pintype "passive"))
      (node (ref "C59") (pin "P$2") (pinfunction "P$2_P$2") (pintype "passive"))
      (node (ref "C6") (pin "P$2") (pinfunction "P$2_P$2") (pintype "passive"))
      (node (ref "C60") (pin "P$2") (pinfunction "P$2_P$2") (pintype "passive"))
      (node (ref "C7") (pin "P$1") (pinfunction "P$1_P$1") (pintype "passive"))
      (node (ref "C8") (pin "P$2") (pinfunction "P$2_P$2") (pintype "passive"))
      (node (ref "C9") (pin "P$2") (pinfunction "P$2_P$2") (pintype "passive"))
      (node (ref "CAN1") (pin "3") (pinfunction "3_3") (pintype "passive"))
      (node (ref "CAN2") (pin "3") (pinfunction "3_3") (pintype "passive"))
      (node (ref "D4") (pin "3") (pinfunction "3_3") (pintype "bidirectional"))
      (node (ref "DG1") (pin "P$1") (pinfunction "P$1_P$1") (pintype "bidirectional"))
      (node (ref "DG2") (pin "P$1") (pinfunction "P$1_P$1") (pintype "bidirectional"))
      (node (ref "ENC") (pin "3") (pinfunction "3_3") (pintype "passive"))
      (node (ref "R6") (pin "P$1") (pinfunction "P$1_P$1") (pintype "passive"))
      (node (ref "R7") (pin "P$2") (pinfunction "P$2_P$2") (pintype "passive"))
      (node (ref "R9") (pin "P$2") (pinfunction "P$2_P$2") (pintype "passive"))
      (node (ref "SH4") (pin "2") (pinfunction "P$2_2") (pintype "bidirectional"))
      (node (ref "SWD") (pin "4") (pinfunction "4_4") (pintype "passive"))
      (node (ref "U1") (pin "32") (pinfunction "PA10_32") (pintype "bidirectional"))
      (node (ref "U1") (pin "49") (pinfunction "THERMALPAD_49") (pintype "bidirectional"))
      (node (ref "U2") (pin "2") (pinfunction "GND_2") (pintype "power_in"))
      (node (ref "U2") (pin "5") (pinfunction "SHDN_5") (pintype "input"))
      (node (ref "U2") (pin "8") (pinfunction "STB_8") (pintype "input"))
      (node (ref "U3") (pin "13") (pinfunction "GND_13") (pintype "bidirectional"))
      (node (ref "U3") (pin "5") (pinfunction "TEST_5") (pintype "bidirectional"))
      (node (ref "U4") (pin "7") (pinfunction "GND_7") (pintype "power_in"))
      (node (ref "U5") (pin "25") (pinfunction "AGND_25") (pintype "bidirectional"))
      (node (ref "U6") (pin "2") (pinfunction "GND_2") (pintype "power_in"))
      (node (ref "U6") (pin "5") (pinfunction "SHDN_5") (pintype "input"))
      (node (ref "U6") (pin "8") (pinfunction "STB_8") (pintype "input"))
    )
    (net (code "69") (name "Net-(C55-PadP$1)") (class "Default")
      (node (ref "C55") (pin "P$1") (pinfunction "P$1_P$1") (pintype "passive"))
      (node (ref "M3") (pin "P$1") (pinfunction "P$1_P$1") (pintype "bidirectional"))
      (node (ref "R10") (pin "P$1") (pinfunction "P$1_P$1") (pintype "passive"))
    )
    (net (code "70") (name "Net-(D2-PadANODE)") (class "Default")
      (node (ref "D2") (pin "ANODE") (pinfunction "ANODE_ANODE") (pintype "power_in"))
      (node (ref "R2") (pin "P$2") (pinfunction "P$2_P$2") (pintype "passive"))
    )
    (net (code "71") (name "Net-(D3-PadANODE)") (class "Default")
      (node (ref "D3") (pin "ANODE") (pinfunction "ANODE_ANODE") (pintype "power_in"))
      (node (ref "R1") (pin "P$2") (pinfunction "P$2_P$2") (pintype "passive"))
    )
    (net (code "72") (name "Net-(U4-VCC)") (class "Default")
      (node (ref "C20") (pin "P$1") (pinfunction "P$1_P$1") (pintype "passive"))
      (node (ref "U4") (pin "3") (pinfunction "VCC_3") (pintype "power_in"))
    )
    (net (code "73") (name "Net-(U5-CPH)") (class "Default")
      (node (ref "C16") (pin "P$1") (pinfunction "P$1_P$1") (pintype "passive"))
      (node (ref "U5") (pin "2") (pinfunction "CPH_2") (pintype "bidirectional"))
    )
    (net (code "74") (name "Net-(U5-CPL)") (class "Default")
      (node (ref "C16") (pin "P$2") (pinfunction "P$2_P$2") (pintype "passive"))
      (node (ref "U5") (pin "1") (pinfunction "CPL_1") (pintype "bidirectional"))
    )
    (net (code "75") (name "Net-(U5-DVDD)") (class "Default")
      (node (ref "C17") (pin "P$2") (pinfunction "P$2_P$2") (pintype "passive"))
      (node (ref "U5") (pin "38") (pinfunction "DVDD_38") (pintype "bidirectional"))
    )
    (net (code "76") (name "Net-(U5-VCP)") (class "Default")
      (node (ref "C15") (pin "P$2") (pinfunction "P$2_P$2") (pintype "passive"))
      (node (ref "U5") (pin "5") (pinfunction "VCP_5") (pintype "bidirectional"))
    )
    (net (code "77") (name "Net-(U5-VGLS)") (class "Default")
      (node (ref "C38") (pin "P$2") (pinfunction "P$2_P$2") (pintype "passive"))
      (node (ref "U5") (pin "40") (pinfunction "VGLS_40") (pintype "bidirectional"))
    )
    (net (code "78") (name "V+") (class "Default")
      (node (ref "C14") (pin "P$1") (pinfunction "P$1_P$1") (pintype "passive"))
      (node (ref "C15") (pin "P$1") (pinfunction "P$1_P$1") (pintype "passive"))
      (node (ref "C19") (pin "P$1") (pinfunction "P$1_P$1") (pintype "passive"))
      (node (ref "C22") (pin "P$1") (pinfunction "P$1_P$1") (pintype "passive"))
      (node (ref "C23") (pin "P$1") (pinfunction "P$1_P$1") (pintype "passive"))
      (node (ref "C24") (pin "P$1") (pinfunction "P$1_P$1") (pintype "passive"))
      (node (ref "C25") (pin "P$1") (pinfunction "P$1_P$1") (pintype "passive"))
      (node (ref "C26") (pin "P$1") (pinfunction "P$1_P$1") (pintype "passive"))
      (node (ref "C27") (pin "P$1") (pinfunction "P$1_P$1") (pintype "passive"))
      (node (ref "C28") (pin "P$1") (pinfunction "P$1_P$1") (pintype "passive"))
      (node (ref "C29") (pin "P$1") (pinfunction "P$1_P$1") (pintype "passive"))
      (node (ref "C30") (pin "P$1") (pinfunction "P$1_P$1") (pintype "passive"))
      (node (ref "C31") (pin "P$1") (pinfunction "P$1_P$1") (pintype "passive"))
      (node (ref "C32") (pin "P$1") (pinfunction "P$1_P$1") (pintype "passive"))
      (node (ref "C33") (pin "P$1") (pinfunction "P$1_P$1") (pintype "passive"))
      (node (ref "C34") (pin "P$1") (pinfunction "P$1_P$1") (pintype "passive"))
      (node (ref "C35") (pin "P$1") (pinfunction "P$1_P$1") (pintype "passive"))
      (node (ref "C36") (pin "P$1") (pinfunction "P$1_P$1") (pintype "passive"))
      (node (ref "C37") (pin "P$1") (pinfunction "P$1_P$1") (pintype "passive"))
      (node (ref "C39") (pin "P$1") (pinfunction "P$1_P$1") (pintype "passive"))
      (node (ref "C40") (pin "P$1") (pinfunction "P$1_P$1") (pintype "passive"))
      (node (ref "C41") (pin "P$1") (pinfunction "P$1_P$1") (pintype "passive"))
      (node (ref "C42") (pin "P$1") (pinfunction "P$1_P$1") (pintype "passive"))
      (node (ref "C43") (pin "P$1") (pinfunction "P$1_P$1") (pintype "passive"))
      (node (ref "C44") (pin "P$1") (pinfunction "P$1_P$1") (pintype "passive"))
      (node (ref "C45") (pin "P$1") (pinfunction "P$1_P$1") (pintype "passive"))
      (node (ref "C46") (pin "P$1") (pinfunction "P$1_P$1") (pintype "passive"))
      (node (ref "C47") (pin "P$1") (pinfunction "P$1_P$1") (pintype "passive"))
      (node (ref "C48") (pin "P$1") (pinfunction "P$1_P$1") (pintype "passive"))
      (node (ref "C49") (pin "P$1") (pinfunction "P$1_P$1") (pintype "passive"))
      (node (ref "C50") (pin "P$1") (pinfunction "P$1_P$1") (pintype "passive"))
      (node (ref "C51") (pin "P$1") (pinfunction "P$1_P$1") (pintype "passive"))
      (node (ref "C52") (pin "P$1") (pinfunction "P$1_P$1") (pintype "passive"))
      (node (ref "C53") (pin "P$1") (pinfunction "P$1_P$1") (pintype "passive"))
      (node (ref "C54") (pin "P$1") (pinfunction "P$1_P$1") (pintype "passive"))
      (node (ref "C61") (pin "P$1") (pinfunction "P$1_P$1") (pintype "passive"))
      (node (ref "C62") (pin "P$1") (pinfunction "P$1_P$1") (pintype "passive"))
      (node (ref "C63") (pin "P$1") (pinfunction "P$1_P$1") (pintype "passive"))
      (node (ref "J1") (pin "1") (pinfunction "1_1") (pintype "passive"))
      (node (ref "J2") (pin "1") (pinfunction "1_1") (pintype "passive"))
      (node (ref "Q1") (pin "5") (pinfunction "D_5") (pintype "passive"))
      (node (ref "Q1") (pin "6") (pinfunction "D_6") (pintype "passive"))
      (node (ref "Q1") (pin "7") (pinfunction "D_7") (pintype "passive"))
      (node (ref "Q1") (pin "8") (pinfunction "D_8") (pintype "passive"))
      (node (ref "Q1") (pin "PAD") (pinfunction "D_PAD") (pintype "passive"))
      (node (ref "Q3") (pin "5") (pinfunction "D_5") (pintype "passive"))
      (node (ref "Q3") (pin "6") (pinfunction "D_6") (pintype "passive"))
      (node (ref "Q3") (pin "7") (pinfunction "D_7") (pintype "passive"))
      (node (ref "Q3") (pin "8") (pinfunction "D_8") (pintype "passive"))
      (node (ref "Q3") (pin "PAD") (pinfunction "D_PAD") (pintype "passive"))
      (node (ref "Q5") (pin "5") (pinfunction "D_5") (pintype "passive"))
      (node (ref "Q5") (pin "6") (pinfunction "D_6") (pintype "passive"))
      (node (ref "Q5") (pin "7") (pinfunction "D_7") (pintype "passive"))
      (node (ref "Q5") (pin "8") (pinfunction "D_8") (pintype "passive"))
      (node (ref "Q5") (pin "PAD") (pinfunction "D_PAD") (pintype "passive"))
      (node (ref "R5") (pin "P$2") (pinfunction "P$2_P$2") (pintype "passive"))
      (node (ref "U4") (pin "1") (pinfunction "VIN_1") (pintype "input"))
      (node (ref "U4") (pin "2") (pinfunction "EN/UVLO_2") (pintype "input"))
      (node (ref "U5") (pin "3") (pinfunction "VM_3") (pintype "bidirectional"))
      (node (ref "U5") (pin "4") (pinfunction "VDRAIN_4") (pintype "bidirectional"))
    )
    (net (code "79") (name "V-") (class "Default")
      (node (ref "C14") (pin "P$2") (pinfunction "P$2_P$2") (pintype "passive"))
      (node (ref "C17") (pin "P$1") (pinfunction "P$1_P$1") (pintype "passive"))
      (node (ref "C19") (pin "P$2") (pinfunction "P$2_P$2") (pintype "passive"))
      (node (ref "C22") (pin "P$2") (pinfunction "P$2_P$2") (pintype "passive"))
      (node (ref "C23") (pin "P$2") (pinfunction "P$2_P$2") (pintype "passive"))
      (node (ref "C24") (pin "P$2") (pinfunction "P$2_P$2") (pintype "passive"))
      (node (ref "C25") (pin "P$2") (pinfunction "P$2_P$2") (pintype "passive"))
      (node (ref "C26") (pin "P$2") (pinfunction "P$2_P$2") (pintype "passive"))
      (node (ref "C27") (pin "P$2") (pinfunction "P$2_P$2") (pintype "passive"))
      (node (ref "C28") (pin "P$2") (pinfunction "P$2_P$2") (pintype "passive"))
      (node (ref "C29") (pin "P$2") (pinfunction "P$2_P$2") (pintype "passive"))
      (node (ref "C30") (pin "P$2") (pinfunction "P$2_P$2") (pintype "passive"))
      (node (ref "C31") (pin "P$2") (pinfunction "P$2_P$2") (pintype "passive"))
      (node (ref "C32") (pin "P$2") (pinfunction "P$2_P$2") (pintype "passive"))
      (node (ref "C33") (pin "P$2") (pinfunction "P$2_P$2") (pintype "passive"))
      (node (ref "C34") (pin "P$2") (pinfunction "P$2_P$2") (pintype "passive"))
      (node (ref "C35") (pin "P$2") (pinfunction "P$2_P$2") (pintype "passive"))
      (node (ref "C36") (pin "P$2") (pinfunction "P$2_P$2") (pintype "passive"))
      (node (ref "C37") (pin "P$2") (pinfunction "P$2_P$2") (pintype "passive"))
      (node (ref "C38") (pin "P$1") (pinfunction "P$1_P$1") (pintype "passive"))
      (node (ref "C39") (pin "P$2") (pinfunction "P$2_P$2") (pintype "passive"))
      (node (ref "C40") (pin "P$2") (pinfunction "P$2_P$2") (pintype "passive"))
      (node (ref "C41") (pin "P$2") (pinfunction "P$2_P$2") (pintype "passive"))
      (node (ref "C42") (pin "P$2") (pinfunction "P$2_P$2") (pintype "passive"))
      (node (ref "C43") (pin "P$2") (pinfunction "P$2_P$2") (pintype "passive"))
      (node (ref "C44") (pin "P$2") (pinfunction "P$2_P$2") (pintype "passive"))
      (node (ref "C45") (pin "P$2") (pinfunction "P$2_P$2") (pintype "passive"))
      (node (ref "C46") (pin "P$2") (pinfunction "P$2_P$2") (pintype "passive"))
      (node (ref "C47") (pin "P$2") (pinfunction "P$2_P$2") (pintype "passive"))
      (node (ref "C48") (pin "P$2") (pinfunction "P$2_P$2") (pintype "passive"))
      (node (ref "C49") (pin "P$2") (pinfunction "P$2_P$2") (pintype "passive"))
      (node (ref "C50") (pin "P$2") (pinfunction "P$2_P$2") (pintype "passive"))
      (node (ref "C51") (pin "P$2") (pinfunction "P$2_P$2") (pintype "passive"))
      (node (ref "C52") (pin "P$2") (pinfunction "P$2_P$2") (pintype "passive"))
      (node (ref "C53") (pin "P$2") (pinfunction "P$2_P$2") (pintype "passive"))
      (node (ref "C54") (pin "P$2") (pinfunction "P$2_P$2") (pintype "passive"))
      (node (ref "C55") (pin "P$2") (pinfunction "P$2_P$2") (pintype "passive"))
      (node (ref "D1") (pin "2") (pinfunction "A_2") (pintype "bidirectional"))
      (node (ref "D5") (pin "2") (pinfunction "A_2") (pintype "bidirectional"))
      (node (ref "D6") (pin "2") (pinfunction "A_2") (pintype "bidirectional"))
      (node (ref "J1") (pin "2") (pinfunction "2_2") (pintype "passive"))
      (node (ref "J2") (pin "2") (pinfunction "2_2") (pintype "passive"))
      (node (ref "R10") (pin "P$2") (pinfunction "P$2_P$2") (pintype "passive"))
      (node (ref "RA") (pin "1") (pinfunction "1_1") (pintype "passive"))
      (node (ref "RB") (pin "1") (pinfunction "1_1") (pintype "passive"))
      (node (ref "RC") (pin "1") (pinfunction "1_1") (pintype "passive"))
      (node (ref "SH1") (pin "2") (pinfunction "P$2_2") (pintype "bidirectional"))
      (node (ref "SH2") (pin "2") (pinfunction "P$2_2") (pintype "bidirectional"))
      (node (ref "SH3") (pin "2") (pinfunction "P$2_2") (pintype "bidirectional"))
      (node (ref "SH4") (pin "1") (pinfunction "P$1_1") (pintype "bidirectional"))
      (node (ref "U5") (pin "39") (pinfunction "GND_39") (pintype "bidirectional"))
      (node (ref "U5") (pin "P1") (pinfunction "PAD_P1") (pintype "bidirectional"))
      (node (ref "U5") (pin "P12") (pinfunction "PAD_P12") (pintype "bidirectional"))
      (node (ref "U5") (pin "P13") (pinfunction "PAD_P13") (pintype "bidirectional"))
      (node (ref "U5") (pin "P14") (pinfunction "PAD_P14") (pintype "bidirectional"))
      (node (ref "U5") (pin "P17") (pinfunction "PAD_P17") (pintype "bidirectional"))
      (node (ref "U5") (pin "P18") (pinfunction "PAD_P18") (pintype "bidirectional"))
      (node (ref "U5") (pin "P19") (pinfunction "PAD_P19") (pintype "bidirectional"))
      (node (ref "U5") (pin "P2") (pinfunction "PAD_P2") (pintype "bidirectional"))
      (node (ref "U5") (pin "P3") (pinfunction "PAD_P3") (pintype "bidirectional"))
      (node (ref "U5") (pin "P7") (pinfunction "PAD_P7") (pintype "bidirectional"))
      (node (ref "U5") (pin "P8") (pinfunction "PAD_P8") (pintype "bidirectional"))
      (node (ref "U5") (pin "P9") (pinfunction "PAD_P9") (pintype "bidirectional"))
      (node (ref "U5") (pin "PAD") (pinfunction "PAD_PAD") (pintype "bidirectional"))
    )
    (net (code "80") (name "unconnected-(M1-PadP$1)") (class "Default")
      (node (ref "M1") (pin "P$1") (pinfunction "P$1_P$1") (pintype "bidirectional"))
    )
    (net (code "81") (name "unconnected-(M2-PadP$1)") (class "Default")
      (node (ref "M2") (pin "P$1") (pinfunction "P$1_P$1") (pintype "bidirectional"))
    )
    (net (code "82") (name "unconnected-(M4-PadP$1)") (class "Default")
      (node (ref "M4") (pin "P$1") (pinfunction "P$1_P$1") (pintype "bidirectional"))
    )
    (net (code "83") (name "unconnected-(SWD-Pad1)") (class "Default")
      (node (ref "SWD") (pin "1") (pinfunction "1_1") (pintype "passive"))
    )
    (net (code "84") (name "unconnected-(U1-PA15-Pad38)") (class "Default")
      (node (ref "U1") (pin "38") (pinfunction "PA15_38") (pintype "bidirectional"))
    )
    (net (code "85") (name "unconnected-(U1-PB3-Pad41)") (class "Default")
      (node (ref "U1") (pin "41") (pinfunction "PB3_41") (pintype "bidirectional"))
    )
    (net (code "86") (name "unconnected-(U1-PB10-Pad22)") (class "Default")
      (node (ref "U1") (pin "22") (pinfunction "PB10_22") (pintype "bidirectional"))
    )
    (net (code "87") (name "unconnected-(U1-PC6-Pad29)") (class "Default")
      (node (ref "U1") (pin "29") (pinfunction "PC6_29") (pintype "bidirectional"))
    )
    (net (code "88") (name "unconnected-(U3-I-Pad14)") (class "Default")
      (node (ref "U3") (pin "14") (pinfunction "I_14") (pintype "bidirectional"))
    )
    (net (code "89") (name "unconnected-(U3-PWM-Pad8)") (class "Default")
      (node (ref "U3") (pin "8") (pinfunction "PWM_8") (pintype "bidirectional"))
    )
    (net (code "90") (name "unconnected-(U3-VDD5V-Pad11)") (class "Default")
      (node (ref "U3") (pin "11") (pinfunction "VDD5V_11") (pintype "bidirectional"))
    )
    (net (code "91") (name "unconnected-(U4-MODE-Pad5)") (class "Default")
      (node (ref "U4") (pin "5") (pinfunction "MODE_5") (pintype "input"))
    )
    (net (code "92") (name "unconnected-(U4-~{RESET}-Pad6)") (class "Default")
      (node (ref "U4") (pin "6") (pinfunction "~{RESET}_6") (pintype "output"))
    )
  )
)
